# bms_ver0_2.net
KiCad netlist of a schematic drawn in EAGLE
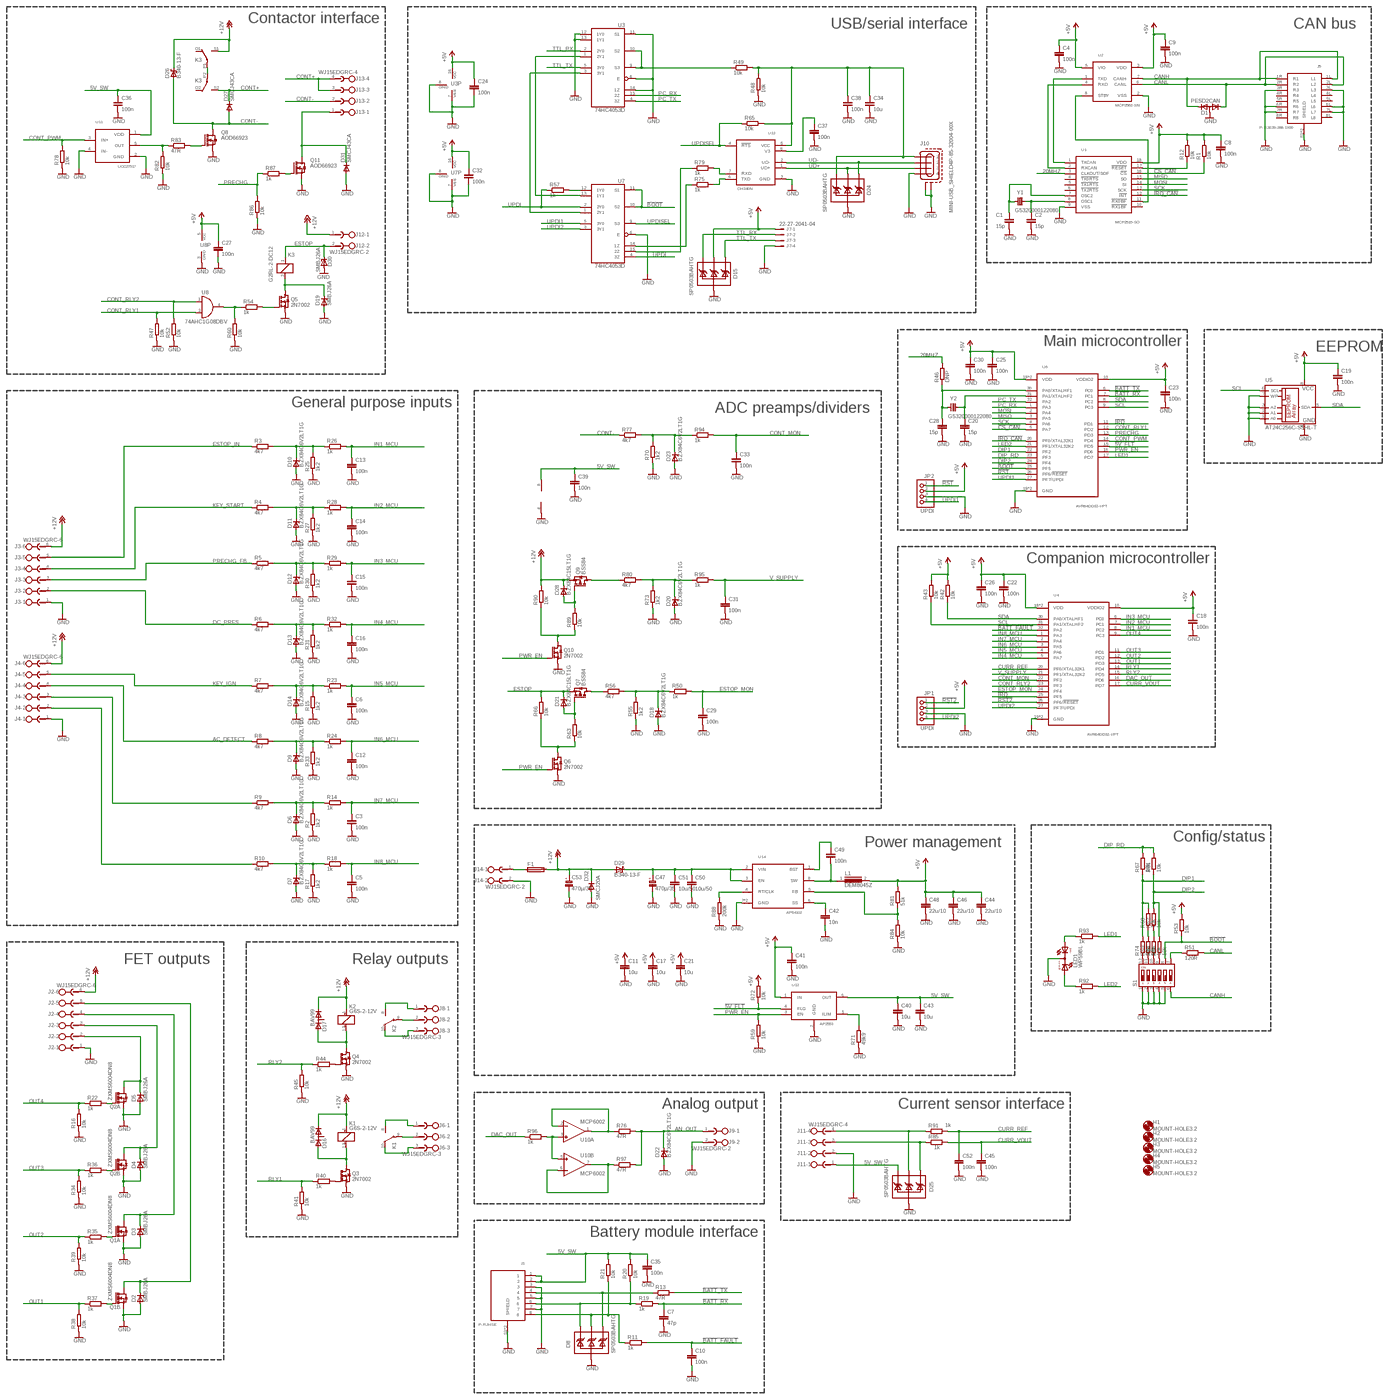
[diagram p0: schematic, sheet 1, overview]
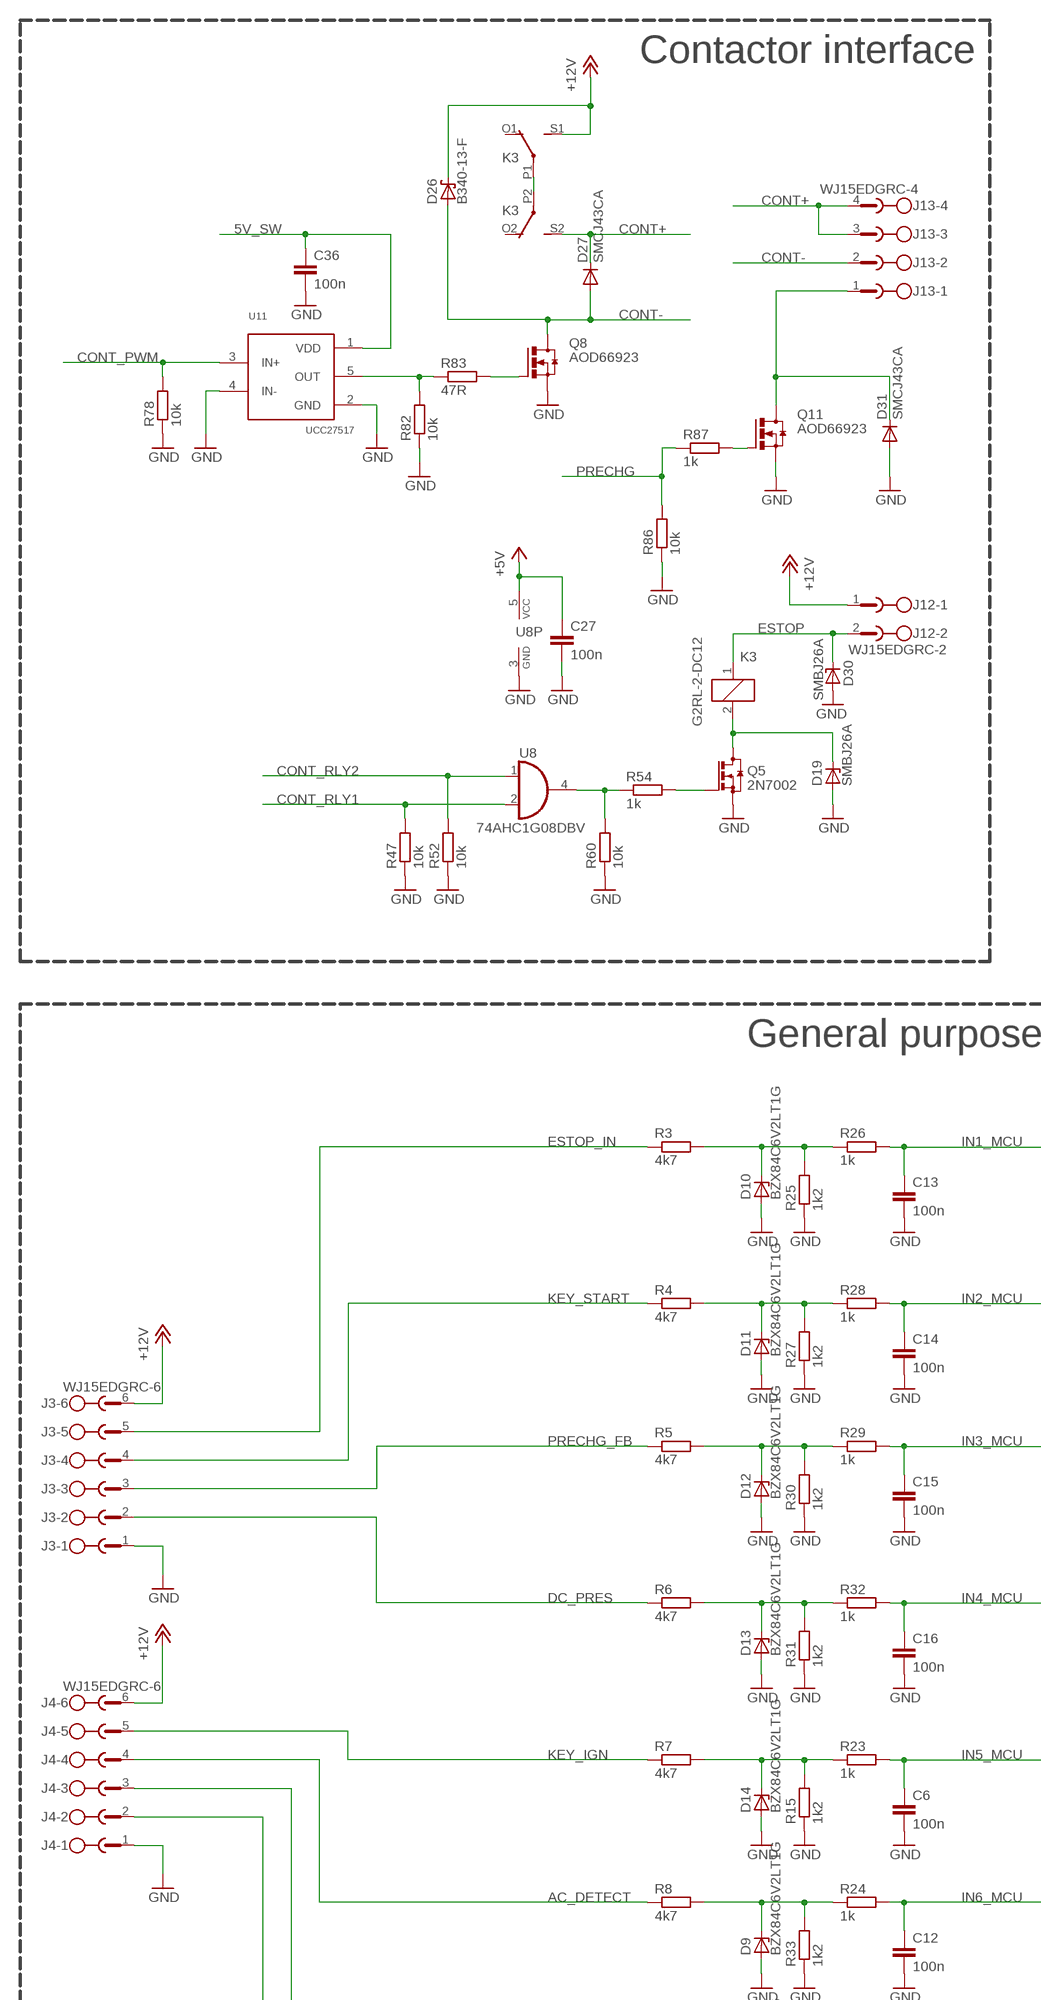
[diagram p1: schematic, sheet 1, part 1 of 4]
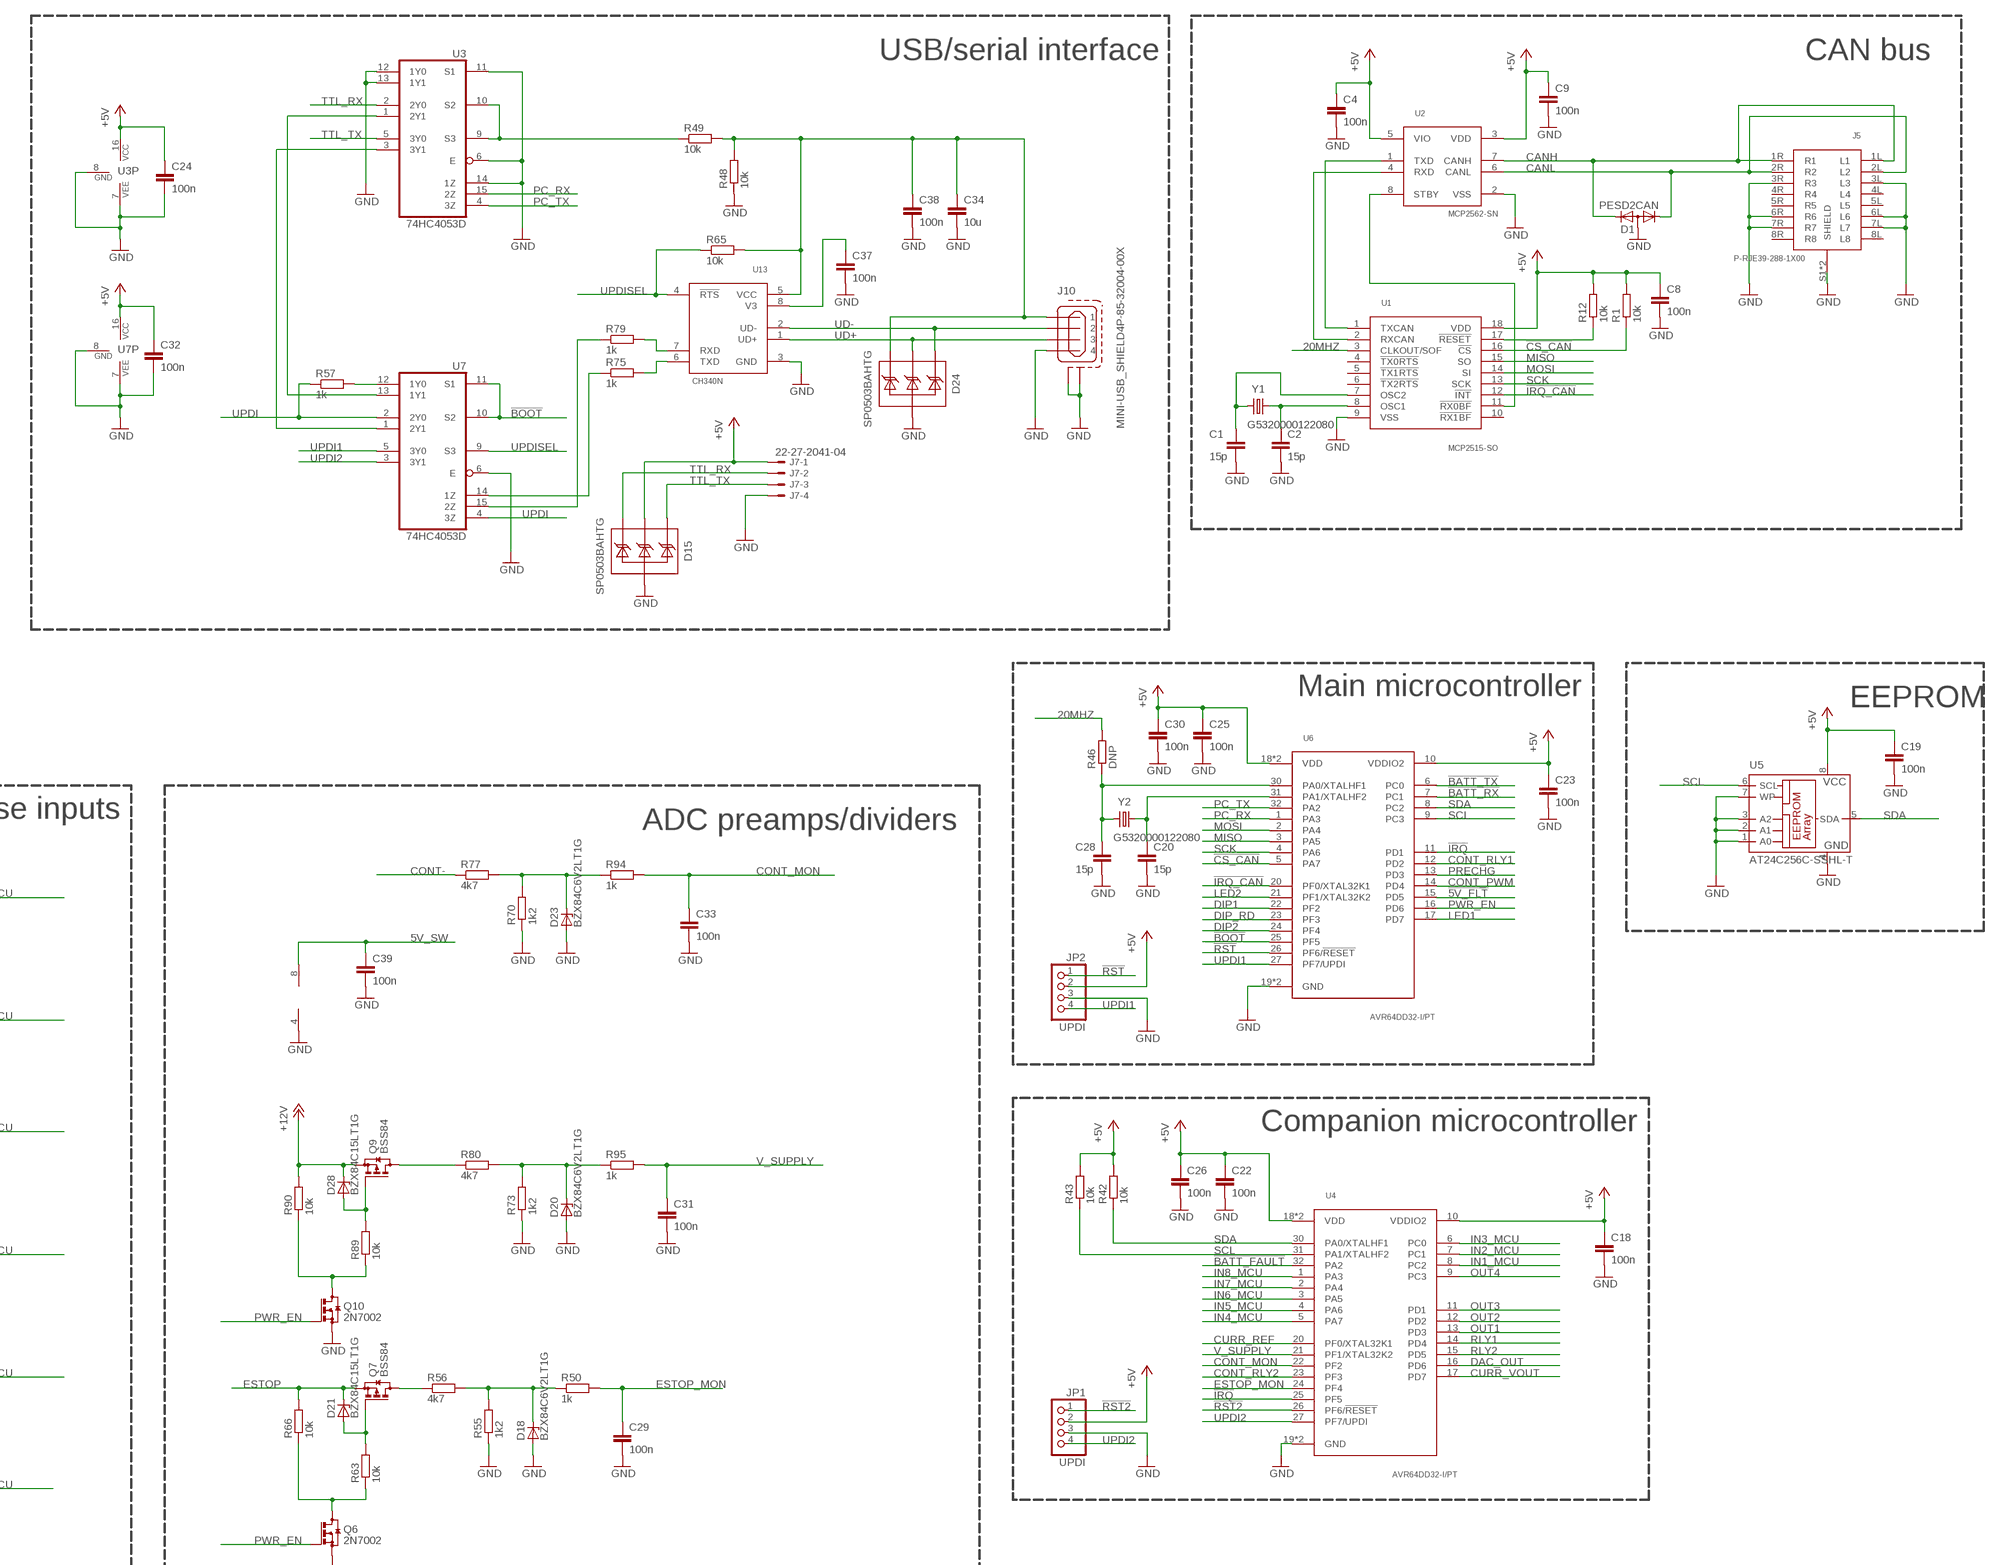
[diagram p2: schematic, sheet 1, part 2 of 4]
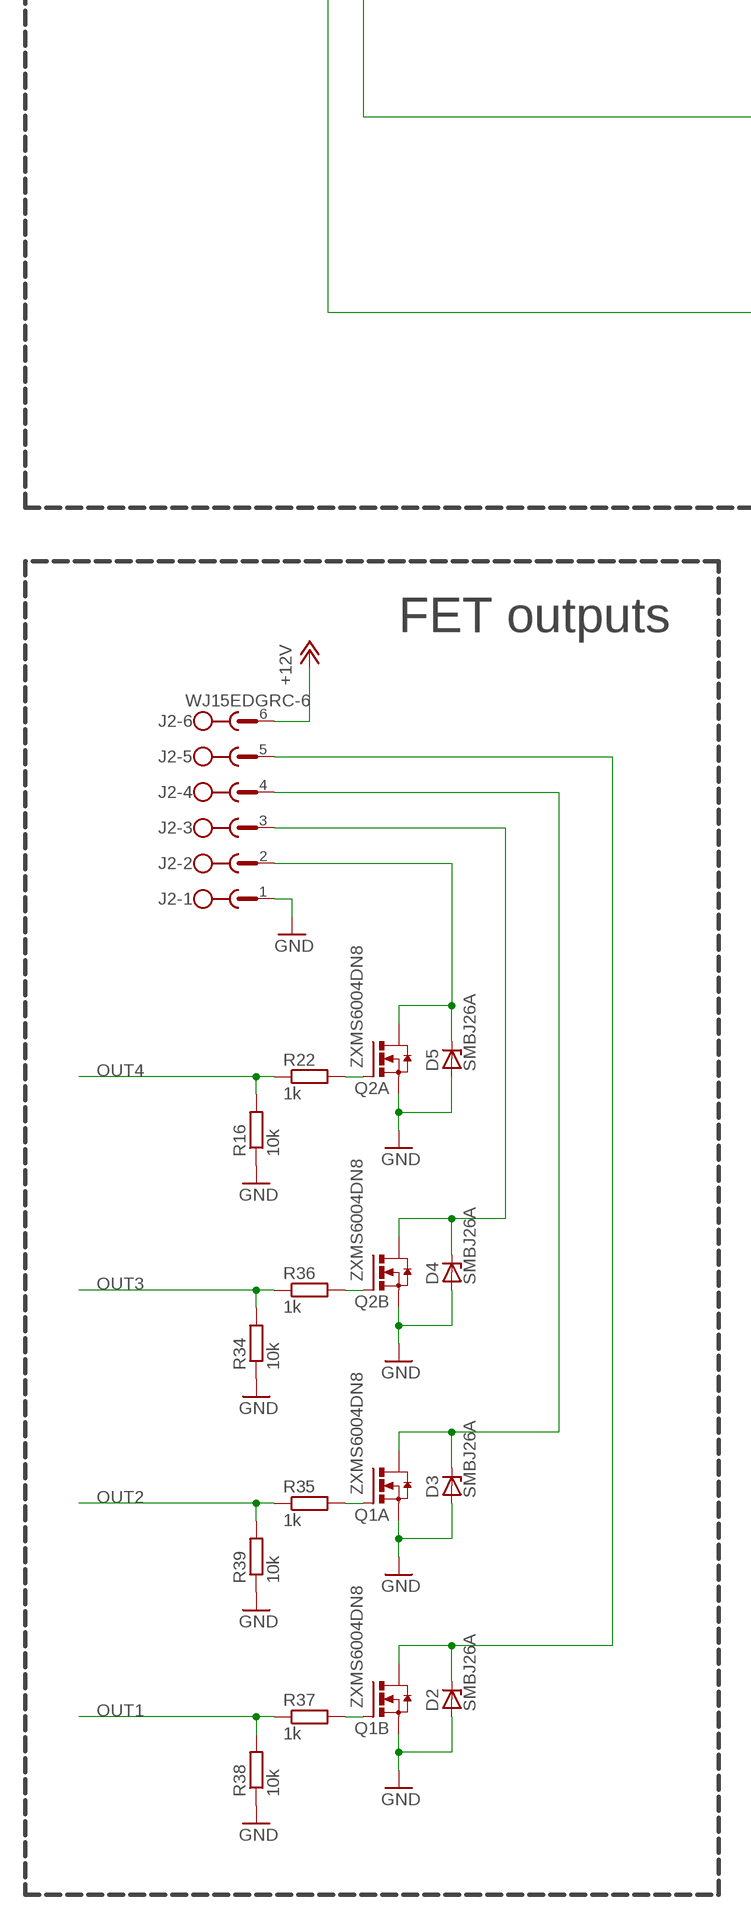
[diagram p3: schematic, sheet 1, part 3 of 4]
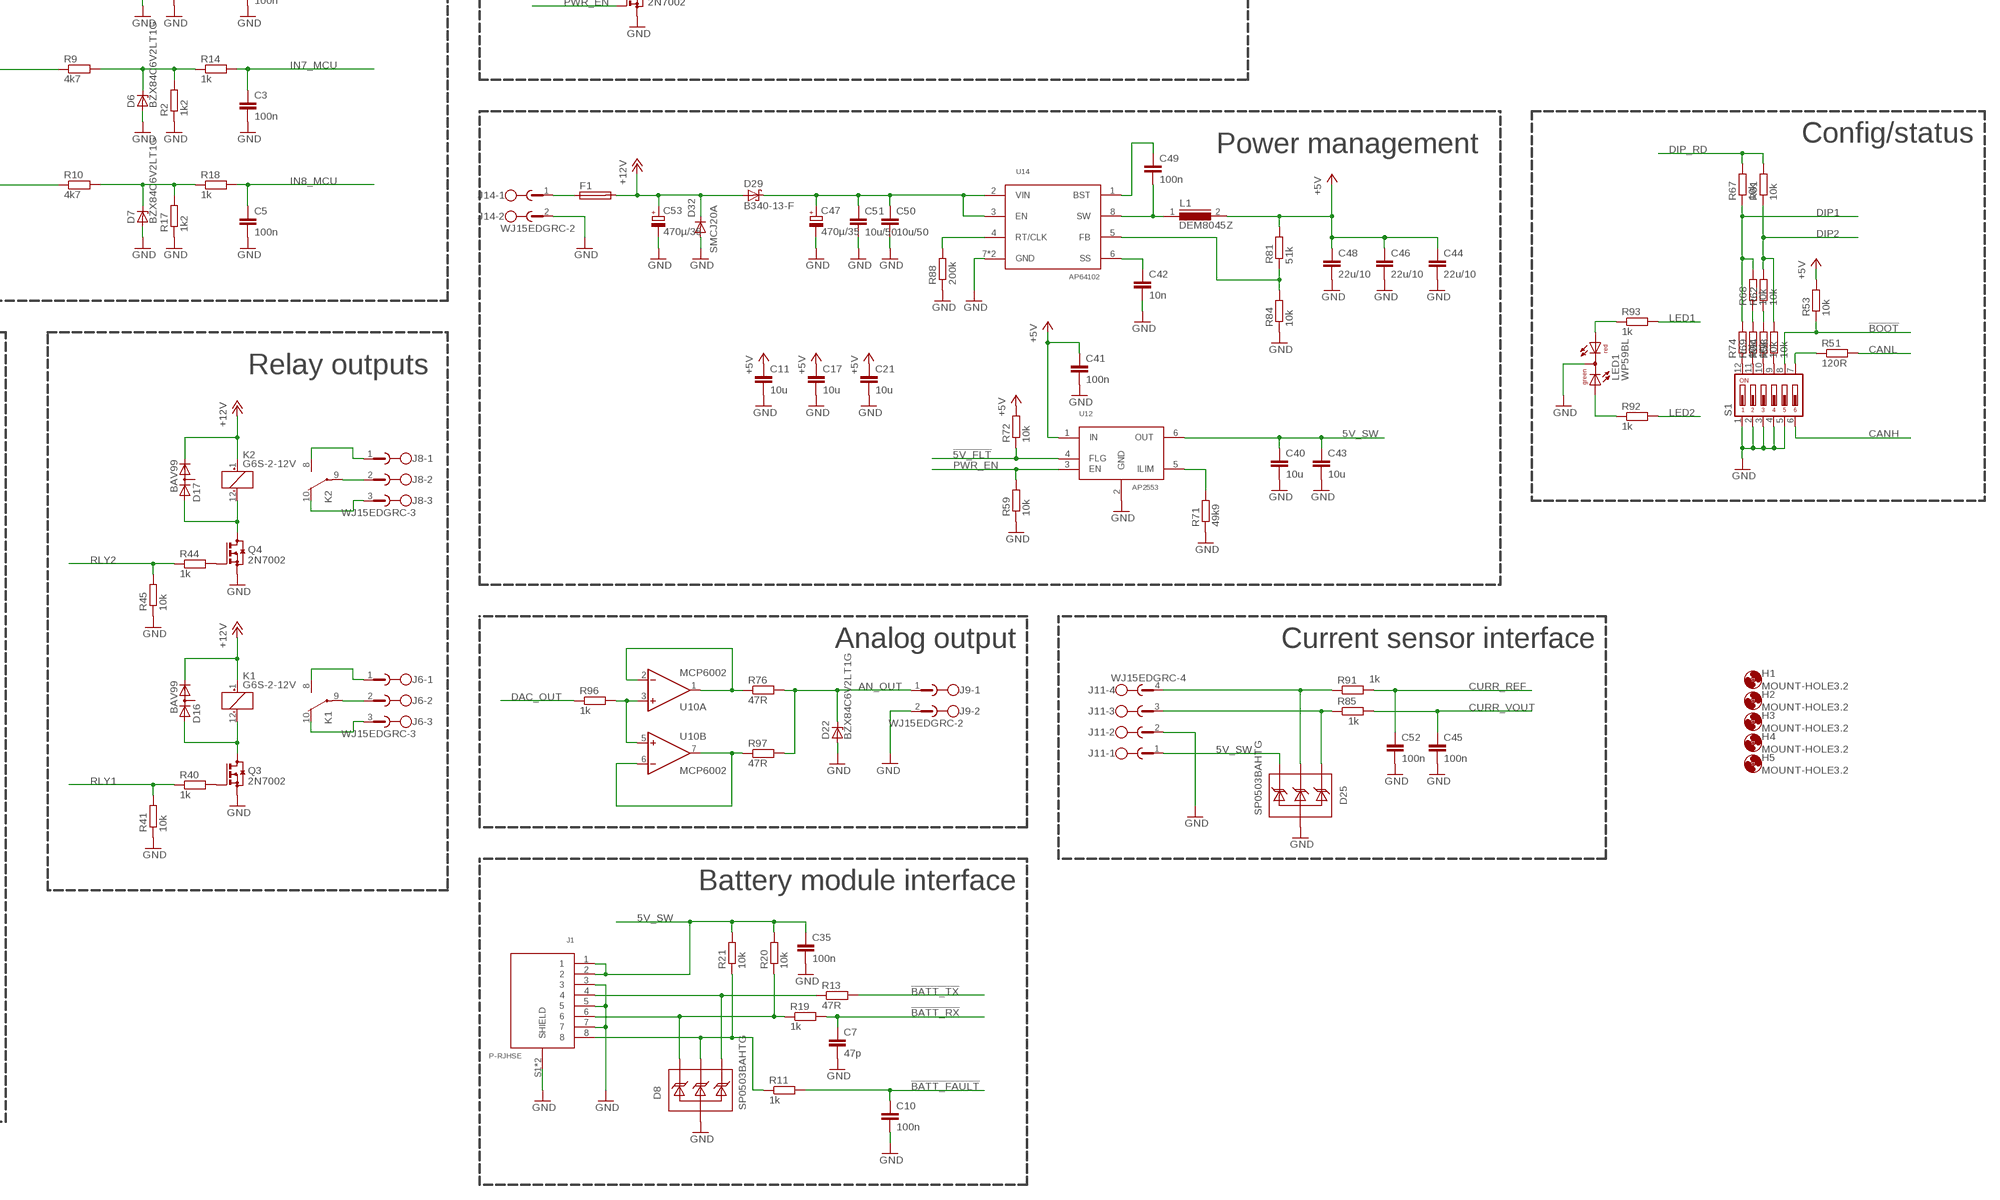
[diagram p4: schematic, sheet 1, part 4 of 4]

(export (version "E")
  (design (tool "Eeschema 10.0.6"))
  (components
    (comp (ref "C1")
      (value "15p")
      (footprint "eagle-import:C0805K")
      (libsource (lib "eagle-import") (part "C-EUC0805K"))
    )
    (comp (ref "C2")
      (value "15p")
      (footprint "eagle-import:C0805K")
      (libsource (lib "eagle-import") (part "C-EUC0805K"))
    )
    (comp (ref "C3")
      (value "100n")
      (footprint "eagle-import:C0805K")
      (libsource (lib "eagle-import") (part "C-EUC0805K"))
    )
    (comp (ref "C4")
      (value "100n")
      (footprint "eagle-import:C0805K")
      (libsource (lib "eagle-import") (part "C-EUC0805K"))
    )
    (comp (ref "C5")
      (value "100n")
      (footprint "eagle-import:C0805K")
      (libsource (lib "eagle-import") (part "C-EUC0805K"))
    )
    (comp (ref "C6")
      (value "100n")
      (footprint "eagle-import:C0805K")
      (libsource (lib "eagle-import") (part "C-EUC0805K"))
    )
    (comp (ref "C7")
      (value "47p")
      (footprint "eagle-import:C0805K")
      (libsource (lib "eagle-import") (part "C-EUC0805K"))
    )
    (comp (ref "C8")
      (value "100n")
      (footprint "eagle-import:C0805K")
      (libsource (lib "eagle-import") (part "C-EUC0805K"))
    )
    (comp (ref "C9")
      (value "100n")
      (footprint "eagle-import:C0805K")
      (libsource (lib "eagle-import") (part "C-EUC0805K"))
    )
    (comp (ref "C10")
      (value "100n")
      (footprint "eagle-import:C0805K")
      (libsource (lib "eagle-import") (part "C-EUC0805K"))
    )
    (comp (ref "C11")
      (value "10u")
      (footprint "eagle-import:C1206K")
      (libsource (lib "eagle-import") (part "C-EUC1206K"))
    )
    (comp (ref "C12")
      (value "100n")
      (footprint "eagle-import:C0805K")
      (libsource (lib "eagle-import") (part "C-EUC0805K"))
    )
    (comp (ref "C13")
      (value "100n")
      (footprint "eagle-import:C0805K")
      (libsource (lib "eagle-import") (part "C-EUC0805K"))
    )
    (comp (ref "C14")
      (value "100n")
      (footprint "eagle-import:C0805K")
      (libsource (lib "eagle-import") (part "C-EUC0805K"))
    )
    (comp (ref "C15")
      (value "100n")
      (footprint "eagle-import:C0805K")
      (libsource (lib "eagle-import") (part "C-EUC0805K"))
    )
    (comp (ref "C16")
      (value "100n")
      (footprint "eagle-import:C0805K")
      (libsource (lib "eagle-import") (part "C-EUC0805K"))
    )
    (comp (ref "C17")
      (value "10u")
      (footprint "eagle-import:C1206K")
      (libsource (lib "eagle-import") (part "C-EUC1206K"))
    )
    (comp (ref "C18")
      (value "100n")
      (footprint "eagle-import:C0805K")
      (libsource (lib "eagle-import") (part "C-EUC0805K"))
    )
    (comp (ref "C19")
      (value "100n")
      (footprint "eagle-import:C0805K")
      (libsource (lib "eagle-import") (part "C-EUC0805K"))
    )
    (comp (ref "C20")
      (value "15p")
      (footprint "eagle-import:C0805K")
      (libsource (lib "eagle-import") (part "C-EUC0805K"))
    )
    (comp (ref "C21")
      (value "10u")
      (footprint "eagle-import:C1206K")
      (libsource (lib "eagle-import") (part "C-EUC1206K"))
    )
    (comp (ref "C22")
      (value "100n")
      (footprint "eagle-import:C0805K")
      (libsource (lib "eagle-import") (part "C-EUC0805K"))
    )
    (comp (ref "C23")
      (value "100n")
      (footprint "eagle-import:C0805K")
      (libsource (lib "eagle-import") (part "C-EUC0805K"))
    )
    (comp (ref "C24")
      (value "100n")
      (footprint "eagle-import:C0805K")
      (libsource (lib "eagle-import") (part "C-EUC0805K"))
    )
    (comp (ref "C25")
      (value "100n")
      (footprint "eagle-import:C0805K")
      (libsource (lib "eagle-import") (part "C-EUC0805K"))
    )
    (comp (ref "C26")
      (value "100n")
      (footprint "eagle-import:C0805K")
      (libsource (lib "eagle-import") (part "C-EUC0805K"))
    )
    (comp (ref "C27")
      (value "100n")
      (footprint "eagle-import:C0805K")
      (libsource (lib "eagle-import") (part "C-EUC0805K"))
    )
    (comp (ref "C28")
      (value "15p")
      (footprint "eagle-import:C0805K")
      (libsource (lib "eagle-import") (part "C-EUC0805K"))
    )
    (comp (ref "C29")
      (value "100n")
      (footprint "eagle-import:C0805K")
      (libsource (lib "eagle-import") (part "C-EUC0805K"))
    )
    (comp (ref "C30")
      (value "100n")
      (footprint "eagle-import:C0805K")
      (libsource (lib "eagle-import") (part "C-EUC0805K"))
    )
    (comp (ref "C31")
      (value "100n")
      (footprint "eagle-import:C0805K")
      (libsource (lib "eagle-import") (part "C-EUC0805K"))
    )
    (comp (ref "C32")
      (value "100n")
      (footprint "eagle-import:C0805K")
      (libsource (lib "eagle-import") (part "C-EUC0805K"))
    )
    (comp (ref "C33")
      (value "100n")
      (footprint "eagle-import:C0805K")
      (libsource (lib "eagle-import") (part "C-EUC0805K"))
    )
    (comp (ref "C34")
      (value "10u")
      (footprint "eagle-import:C1206K")
      (libsource (lib "eagle-import") (part "C-EUC1206K"))
    )
    (comp (ref "C35")
      (value "100n")
      (footprint "eagle-import:C0805K")
      (libsource (lib "eagle-import") (part "C-EUC0805K"))
    )
    (comp (ref "C36")
      (value "100n")
      (footprint "eagle-import:C0805K")
      (libsource (lib "eagle-import") (part "C-EUC0805K"))
    )
    (comp (ref "C37")
      (value "100n")
      (footprint "eagle-import:C0805K")
      (libsource (lib "eagle-import") (part "C-EUC0805K"))
    )
    (comp (ref "C38")
      (value "100n")
      (footprint "eagle-import:C0805K")
      (libsource (lib "eagle-import") (part "C-EUC0805K"))
    )
    (comp (ref "C39")
      (value "100n")
      (footprint "eagle-import:C0805K")
      (libsource (lib "eagle-import") (part "C-EUC0805K"))
    )
    (comp (ref "C40")
      (value "10u")
      (footprint "eagle-import:C1206K")
      (libsource (lib "eagle-import") (part "C-EUC1206K"))
    )
    (comp (ref "C41")
      (value "100n")
      (footprint "eagle-import:C0805K")
      (libsource (lib "eagle-import") (part "C-EUC0805K"))
    )
    (comp (ref "C42")
      (value "10n")
      (footprint "eagle-import:C0805K")
      (libsource (lib "eagle-import") (part "C-EUC0805K"))
    )
    (comp (ref "C43")
      (value "10u")
      (footprint "eagle-import:C1206K")
      (libsource (lib "eagle-import") (part "C-EUC1206K"))
    )
    (comp (ref "C44")
      (value "22u/10")
      (footprint "eagle-import:C1206K")
      (libsource (lib "eagle-import") (part "C-EUC1206K"))
    )
    (comp (ref "C45")
      (value "100n")
      (footprint "eagle-import:C0805K")
      (libsource (lib "eagle-import") (part "C-EUC0805K"))
    )
    (comp (ref "C46")
      (value "22u/10")
      (footprint "eagle-import:C1206K")
      (libsource (lib "eagle-import") (part "C-EUC1206K"))
    )
    (comp (ref "C47")
      (value "470µ/35")
      (footprint "eagle-import:E5-10,5")
      (libsource (lib "eagle-import") (part "CPOL-EUE5-10.5"))
    )
    (comp (ref "C48")
      (value "22u/10")
      (footprint "eagle-import:C1206K")
      (libsource (lib "eagle-import") (part "C-EUC1206K"))
    )
    (comp (ref "C49")
      (value "100n")
      (footprint "eagle-import:C0805K")
      (libsource (lib "eagle-import") (part "C-EUC0805K"))
    )
    (comp (ref "C50")
      (value "10u/50")
      (footprint "eagle-import:C1206K")
      (libsource (lib "eagle-import") (part "C-EUC1206K"))
    )
    (comp (ref "C51")
      (value "10u/50")
      (footprint "eagle-import:C1206K")
      (libsource (lib "eagle-import") (part "C-EUC1206K"))
    )
    (comp (ref "C52")
      (value "100n")
      (footprint "eagle-import:C0805K")
      (libsource (lib "eagle-import") (part "C-EUC0805K"))
    )
    (comp (ref "C53")
      (value "470µ/35")
      (footprint "eagle-import:E5-10,5")
      (libsource (lib "eagle-import") (part "CPOL-EUE5-10.5"))
    )
    (comp (ref "D1")
      (value "PESD2CAN")
      (footprint "eagle-import:SOT23")
      (libsource (lib "eagle-import") (part "DIODE-2CA|ACSOT23"))
    )
    (comp (ref "D2")
      (value "SMBJ26A")
      (footprint "eagle-import:SMB")
      (libsource (lib "eagle-import") (part "ZENER-DIODESMB"))
    )
    (comp (ref "D3")
      (value "SMBJ26A")
      (footprint "eagle-import:SMB")
      (libsource (lib "eagle-import") (part "ZENER-DIODESMB"))
    )
    (comp (ref "D4")
      (value "SMBJ26A")
      (footprint "eagle-import:SMB")
      (libsource (lib "eagle-import") (part "ZENER-DIODESMB"))
    )
    (comp (ref "D5")
      (value "SMBJ26A")
      (footprint "eagle-import:SMB")
      (libsource (lib "eagle-import") (part "ZENER-DIODESMB"))
    )
    (comp (ref "D6")
      (value "BZX84C6V2LT1G")
      (footprint "eagle-import:SOT23")
      (libsource (lib "eagle-import") (part "ZENER-DIODESOT23"))
    )
    (comp (ref "D7")
      (value "BZX84C6V2LT1G")
      (footprint "eagle-import:SOT23")
      (libsource (lib "eagle-import") (part "ZENER-DIODESOT23"))
    )
    (comp (ref "D8")
      (value "SP0503BAHTG")
      (footprint "eagle-import:SOT143")
      (libsource (lib "eagle-import") (part "SP0503BAHTG"))
    )
    (comp (ref "D9")
      (value "BZX84C6V2LT1G")
      (footprint "eagle-import:SOT23")
      (libsource (lib "eagle-import") (part "ZENER-DIODESOT23"))
    )
    (comp (ref "D10")
      (value "BZX84C6V2LT1G")
      (footprint "eagle-import:SOT23")
      (libsource (lib "eagle-import") (part "ZENER-DIODESOT23"))
    )
    (comp (ref "D11")
      (value "BZX84C6V2LT1G")
      (footprint "eagle-import:SOT23")
      (libsource (lib "eagle-import") (part "ZENER-DIODESOT23"))
    )
    (comp (ref "D12")
      (value "BZX84C6V2LT1G")
      (footprint "eagle-import:SOT23")
      (libsource (lib "eagle-import") (part "ZENER-DIODESOT23"))
    )
    (comp (ref "D13")
      (value "BZX84C6V2LT1G")
      (footprint "eagle-import:SOT23")
      (libsource (lib "eagle-import") (part "ZENER-DIODESOT23"))
    )
    (comp (ref "D14")
      (value "BZX84C6V2LT1G")
      (footprint "eagle-import:SOT23")
      (libsource (lib "eagle-import") (part "ZENER-DIODESOT23"))
    )
    (comp (ref "D15")
      (value "SP0503BAHTG")
      (footprint "eagle-import:SOT143")
      (libsource (lib "eagle-import") (part "SP0503BAHTG"))
    )
    (comp (ref "D16")
      (value "BAV99")
      (footprint "eagle-import:SOT23")
      (libsource (lib "eagle-import") (part "BAV199"))
    )
    (comp (ref "D17")
      (value "BAV99")
      (footprint "eagle-import:SOT23")
      (libsource (lib "eagle-import") (part "BAV199"))
    )
    (comp (ref "D18")
      (value "BZX84C6V2LT1G")
      (footprint "eagle-import:SOT23")
      (libsource (lib "eagle-import") (part "ZENER-DIODESOT23"))
    )
    (comp (ref "D19")
      (value "SMBJ26A")
      (footprint "eagle-import:SMB")
      (libsource (lib "eagle-import") (part "ZENER-DIODESMB"))
    )
    (comp (ref "D20")
      (value "BZX84C6V2LT1G")
      (footprint "eagle-import:SOT23")
      (libsource (lib "eagle-import") (part "ZENER-DIODESOT23"))
    )
    (comp (ref "D21")
      (value "BZX84C15LT1G")
      (footprint "eagle-import:SOT23")
      (libsource (lib "eagle-import") (part "ZENER-DIODESOT23"))
    )
    (comp (ref "D22")
      (value "BZX84C6V2LT1G")
      (footprint "eagle-import:SOT23")
      (libsource (lib "eagle-import") (part "ZENER-DIODESOT23"))
    )
    (comp (ref "D23")
      (value "BZX84C6V2LT1G")
      (footprint "eagle-import:SOT23")
      (libsource (lib "eagle-import") (part "ZENER-DIODESOT23"))
    )
    (comp (ref "D24")
      (value "SP0503BAHTG")
      (footprint "eagle-import:SOT143")
      (libsource (lib "eagle-import") (part "SP0503BAHTG"))
    )
    (comp (ref "D25")
      (value "SP0503BAHTG")
      (footprint "eagle-import:SOT143")
      (libsource (lib "eagle-import") (part "SP0503BAHTG"))
    )
    (comp (ref "D26")
      (value "B340-13-F")
      (footprint "eagle-import:SMC")
      (libsource (lib "eagle-import") (part "SCHOTTKY-DIODESMC"))
    )
    (comp (ref "D27")
      (value "SMCJ43CA")
      (footprint "eagle-import:SMC")
      (libsource (lib "eagle-import") (part "DIODE-SMC"))
    )
    (comp (ref "D28")
      (value "BZX84C15LT1G")
      (footprint "eagle-import:SOT23")
      (libsource (lib "eagle-import") (part "ZENER-DIODESOT23"))
    )
    (comp (ref "D29")
      (value "B340-13-F")
      (footprint "eagle-import:SMC")
      (libsource (lib "eagle-import") (part "SCHOTTKY-DIODESMC"))
    )
    (comp (ref "D30")
      (value "SMBJ26A")
      (footprint "eagle-import:SMB")
      (libsource (lib "eagle-import") (part "ZENER-DIODESMB"))
    )
    (comp (ref "D31")
      (value "SMCJ43CA")
      (footprint "eagle-import:SMC")
      (libsource (lib "eagle-import") (part "DIODE-SMC"))
    )
    (comp (ref "D32")
      (value "SMCJ20A")
      (footprint "eagle-import:SMC")
      (libsource (lib "eagle-import") (part "DIODE-SMC"))
    )
    (comp (ref "F1")
      (value "3568")
      (footprint "eagle-import:3568")
      (libsource (lib "eagle-import") (part "3568"))
    )
    (comp (ref "H1")
      (value "MOUNT-HOLE3.2")
      (footprint "eagle-import:3,2")
      (libsource (lib "eagle-import") (part "MOUNT-HOLE3.2"))
    )
    (comp (ref "H2")
      (value "MOUNT-HOLE3.2")
      (footprint "eagle-import:3,2")
      (libsource (lib "eagle-import") (part "MOUNT-HOLE3.2"))
    )
    (comp (ref "H3")
      (value "MOUNT-HOLE3.2")
      (footprint "eagle-import:3,2")
      (libsource (lib "eagle-import") (part "MOUNT-HOLE3.2"))
    )
    (comp (ref "H4")
      (value "MOUNT-HOLE3.2")
      (footprint "eagle-import:3,2")
      (libsource (lib "eagle-import") (part "MOUNT-HOLE3.2"))
    )
    (comp (ref "H5")
      (value "MOUNT-HOLE3.2")
      (footprint "eagle-import:3,2")
      (libsource (lib "eagle-import") (part "MOUNT-HOLE3.2"))
    )
    (comp (ref "J1")
      (value "P-RJHSE")
      (footprint "eagle-import:P-RJHSE")
      (libsource (lib "eagle-import") (part "P-RJHSE"))
    )
    (comp (ref "J2")
      (value "WJ15EDGRC-6")
      (footprint "eagle-import:WJ15EDGRC-3.81-6")
      (libsource (lib "eagle-import") (part "WJ15EDGRC-6"))
    )
    (comp (ref "J3")
      (value "WJ15EDGRC-6")
      (footprint "eagle-import:WJ15EDGRC-3.81-6")
      (libsource (lib "eagle-import") (part "WJ15EDGRC-6"))
    )
    (comp (ref "J4")
      (value "WJ15EDGRC-6")
      (footprint "eagle-import:WJ15EDGRC-3.81-6")
      (libsource (lib "eagle-import") (part "WJ15EDGRC-6"))
    )
    (comp (ref "J5")
      (value "P-RJE39-288-1X00")
      (footprint "eagle-import:P-RJE39-288-1X00")
      (libsource (lib "eagle-import") (part "P-RJE39-288-1X00"))
    )
    (comp (ref "J6")
      (value "WJ15EDGRC-3")
      (footprint "eagle-import:WJ15EDGRC-3.81-3")
      (libsource (lib "eagle-import") (part "WJ15EDGRC-3"))
    )
    (comp (ref "J7")
      (value "22-27-2041-04")
      (footprint "eagle-import:6410-04")
      (libsource (lib "eagle-import") (part "22-?-0427-2041"))
    )
    (comp (ref "J8")
      (value "WJ15EDGRC-3")
      (footprint "eagle-import:WJ15EDGRC-3.81-3")
      (libsource (lib "eagle-import") (part "WJ15EDGRC-3"))
    )
    (comp (ref "J9")
      (value "WJ15EDGRC-2")
      (footprint "eagle-import:WJ15EDGRC-3.81-2")
      (libsource (lib "eagle-import") (part "WJ15EDGRC-2"))
    )
    (comp (ref "J10")
      (value "MINI-USB_SHIELD4P-85-32004-00X")
      (footprint "eagle-import:85-32004-00X")
      (libsource (lib "eagle-import") (part "MINI-USB_SHIELD4P-85-32004-00X"))
    )
    (comp (ref "J11")
      (value "WJ15EDGRC-4")
      (footprint "eagle-import:WJ15EDGRC-3.81-4")
      (libsource (lib "eagle-import") (part "WJ15EDGRC-4"))
    )
    (comp (ref "J12")
      (value "WJ15EDGRC-2")
      (footprint "eagle-import:WJ15EDGRC-3.81-2")
      (libsource (lib "eagle-import") (part "WJ15EDGRC-2"))
    )
    (comp (ref "J13")
      (value "WJ15EDGRC-4")
      (footprint "eagle-import:WJ15EDGRC-3.81-4")
      (libsource (lib "eagle-import") (part "WJ15EDGRC-4"))
    )
    (comp (ref "J14")
      (value "WJ15EDGRC-2")
      (footprint "eagle-import:WJ15EDGRC-3.81-2")
      (libsource (lib "eagle-import") (part "WJ15EDGRC-2"))
    )
    (comp (ref "JP1")
      (value "UPDI")
      (footprint "eagle-import:1X04")
      (libsource (lib "eagle-import") (part "PINHD-1X4"))
    )
    (comp (ref "JP2")
      (value "UPDI")
      (footprint "eagle-import:1X04")
      (libsource (lib "eagle-import") (part "PINHD-1X4"))
    )
    (comp (ref "K1")
      (value "G6S-2-12V")
      (footprint "eagle-import:TXD2")
      (fields (field (name "MPN") "TXS2-12V"))
      (libsource (lib "eagle-import") (part "TX?-S212V"))
    )
    (comp (ref "K2")
      (value "G6S-2-12V")
      (footprint "eagle-import:TXD2")
      (fields (field (name "MPN") "TXS2-12V"))
      (libsource (lib "eagle-import") (part "TX?-S212V"))
    )
    (comp (ref "K3")
      (value "G2RL-2-DC12")
      (footprint "eagle-import:G2R2")
      (fields (field (name "MF") "OMRON COMPONENTS USA") (field (name "MPN") "G2R-2-DC6"))
      (libsource (lib "eagle-import") (part "G2R2"))
    )
    (comp (ref "L1")
      (value "DEM8045Z")
      (footprint "eagle-import:DEM8045Z")
      (libsource (lib "eagle-import") (part "DEM8045Z"))
    )
    (comp (ref "LED1")
      (value "WP59BL")
      (footprint "eagle-import:WP59BL")
      (fields (field (name "MF") "VISHAY SEMICONDUCTOR"))
      (libsource (lib "eagle-import") (part "WP59BL"))
    )
    (comp (ref "Q1")
      (value "ZXMS6004DN8")
      (footprint "eagle-import:SO-08")
      (fields (field (name "MOUSER") "621-ZXMS6004DN8-13"))
      (libsource (lib "eagle-import") (part "IRF8313P"))
    )
    (comp (ref "Q2")
      (value "ZXMS6004DN8")
      (footprint "eagle-import:SO-08")
      (fields (field (name "MOUSER") "621-ZXMS6004DN8-13"))
      (libsource (lib "eagle-import") (part "IRF8313P"))
    )
    (comp (ref "Q3")
      (value "2N7002")
      (footprint "eagle-import:SOT23")
      (libsource (lib "eagle-import") (part "BSS123"))
    )
    (comp (ref "Q4")
      (value "2N7002")
      (footprint "eagle-import:SOT23")
      (libsource (lib "eagle-import") (part "BSS123"))
    )
    (comp (ref "Q5")
      (value "2N7002")
      (footprint "eagle-import:SOT23")
      (libsource (lib "eagle-import") (part "BSS123"))
    )
    (comp (ref "Q6")
      (value "2N7002")
      (footprint "eagle-import:SOT23")
      (libsource (lib "eagle-import") (part "BSS123"))
    )
    (comp (ref "Q7")
      (value "BSS84")
      (footprint "eagle-import:SOT23")
      (libsource (lib "eagle-import") (part "BSS84"))
    )
    (comp (ref "Q8")
      (value "AOD66923")
      (footprint "eagle-import:D-PAK_TO252AA")
      (libsource (lib "eagle-import") (part "N-MOSFETR"))
    )
    (comp (ref "Q9")
      (value "BSS84")
      (footprint "eagle-import:SOT23")
      (libsource (lib "eagle-import") (part "BSS84"))
    )
    (comp (ref "Q10")
      (value "2N7002")
      (footprint "eagle-import:SOT23")
      (libsource (lib "eagle-import") (part "BSS123"))
    )
    (comp (ref "Q11")
      (value "AOD66923")
      (footprint "eagle-import:D-PAK_TO252AA")
      (libsource (lib "eagle-import") (part "N-MOSFETR"))
    )
    (comp (ref "R1")
      (value "10k")
      (footprint "eagle-import:R0805")
      (libsource (lib "eagle-import") (part "R-EU_R0805"))
    )
    (comp (ref "R2")
      (value "1k2")
      (footprint "eagle-import:R0805")
      (libsource (lib "eagle-import") (part "R-EU_R0805"))
    )
    (comp (ref "R3")
      (value "4k7")
      (footprint "eagle-import:R1206")
      (libsource (lib "eagle-import") (part "R-EU_R1206"))
    )
    (comp (ref "R4")
      (value "4k7")
      (footprint "eagle-import:R1206")
      (libsource (lib "eagle-import") (part "R-EU_R1206"))
    )
    (comp (ref "R5")
      (value "4k7")
      (footprint "eagle-import:R1206")
      (libsource (lib "eagle-import") (part "R-EU_R1206"))
    )
    (comp (ref "R6")
      (value "4k7")
      (footprint "eagle-import:R1206")
      (libsource (lib "eagle-import") (part "R-EU_R1206"))
    )
    (comp (ref "R7")
      (value "4k7")
      (footprint "eagle-import:R1206")
      (libsource (lib "eagle-import") (part "R-EU_R1206"))
    )
    (comp (ref "R8")
      (value "4k7")
      (footprint "eagle-import:R1206")
      (libsource (lib "eagle-import") (part "R-EU_R1206"))
    )
    (comp (ref "R9")
      (value "4k7")
      (footprint "eagle-import:R1206")
      (libsource (lib "eagle-import") (part "R-EU_R1206"))
    )
    (comp (ref "R10")
      (value "4k7")
      (footprint "eagle-import:R1206")
      (libsource (lib "eagle-import") (part "R-EU_R1206"))
    )
    (comp (ref "R11")
      (value "1k")
      (footprint "eagle-import:R0805")
      (libsource (lib "eagle-import") (part "R-EU_R0805"))
    )
    (comp (ref "R12")
      (value "10k")
      (footprint "eagle-import:R0805")
      (libsource (lib "eagle-import") (part "R-EU_R0805"))
    )
    (comp (ref "R13")
      (value "47R")
      (footprint "eagle-import:R0805")
      (libsource (lib "eagle-import") (part "R-EU_R0805"))
    )
    (comp (ref "R14")
      (value "1k")
      (footprint "eagle-import:R0805")
      (libsource (lib "eagle-import") (part "R-EU_R0805"))
    )
    (comp (ref "R15")
      (value "1k2")
      (footprint "eagle-import:R0805")
      (libsource (lib "eagle-import") (part "R-EU_R0805"))
    )
    (comp (ref "R16")
      (value "10k")
      (footprint "eagle-import:R0805")
      (libsource (lib "eagle-import") (part "R-EU_R0805"))
    )
    (comp (ref "R17")
      (value "1k2")
      (footprint "eagle-import:R0805")
      (libsource (lib "eagle-import") (part "R-EU_R0805"))
    )
    (comp (ref "R18")
      (value "1k")
      (footprint "eagle-import:R0805")
      (libsource (lib "eagle-import") (part "R-EU_R0805"))
    )
    (comp (ref "R19")
      (value "1k")
      (footprint "eagle-import:R0805")
      (libsource (lib "eagle-import") (part "R-EU_R0805"))
    )
    (comp (ref "R20")
      (value "10k")
      (footprint "eagle-import:R0805")
      (libsource (lib "eagle-import") (part "R-EU_R0805"))
    )
    (comp (ref "R21")
      (value "10k")
      (footprint "eagle-import:R0805")
      (libsource (lib "eagle-import") (part "R-EU_R0805"))
    )
    (comp (ref "R22")
      (value "1k")
      (footprint "eagle-import:R0805")
      (libsource (lib "eagle-import") (part "R-EU_R0805"))
    )
    (comp (ref "R23")
      (value "1k")
      (footprint "eagle-import:R0805")
      (libsource (lib "eagle-import") (part "R-EU_R0805"))
    )
    (comp (ref "R24")
      (value "1k")
      (footprint "eagle-import:R0805")
      (libsource (lib "eagle-import") (part "R-EU_R0805"))
    )
    (comp (ref "R25")
      (value "1k2")
      (footprint "eagle-import:R0805")
      (libsource (lib "eagle-import") (part "R-EU_R0805"))
    )
    (comp (ref "R26")
      (value "1k")
      (footprint "eagle-import:R0805")
      (libsource (lib "eagle-import") (part "R-EU_R0805"))
    )
    (comp (ref "R27")
      (value "1k2")
      (footprint "eagle-import:R0805")
      (libsource (lib "eagle-import") (part "R-EU_R0805"))
    )
    (comp (ref "R28")
      (value "1k")
      (footprint "eagle-import:R0805")
      (libsource (lib "eagle-import") (part "R-EU_R0805"))
    )
    (comp (ref "R29")
      (value "1k")
      (footprint "eagle-import:R0805")
      (libsource (lib "eagle-import") (part "R-EU_R0805"))
    )
    (comp (ref "R30")
      (value "1k2")
      (footprint "eagle-import:R0805")
      (libsource (lib "eagle-import") (part "R-EU_R0805"))
    )
    (comp (ref "R31")
      (value "1k2")
      (footprint "eagle-import:R0805")
      (libsource (lib "eagle-import") (part "R-EU_R0805"))
    )
    (comp (ref "R32")
      (value "1k")
      (footprint "eagle-import:R0805")
      (libsource (lib "eagle-import") (part "R-EU_R0805"))
    )
    (comp (ref "R33")
      (value "1k2")
      (footprint "eagle-import:R0805")
      (libsource (lib "eagle-import") (part "R-EU_R0805"))
    )
    (comp (ref "R34")
      (value "10k")
      (footprint "eagle-import:R0805")
      (libsource (lib "eagle-import") (part "R-EU_R0805"))
    )
    (comp (ref "R35")
      (value "1k")
      (footprint "eagle-import:R0805")
      (libsource (lib "eagle-import") (part "R-EU_R0805"))
    )
    (comp (ref "R36")
      (value "1k")
      (footprint "eagle-import:R0805")
      (libsource (lib "eagle-import") (part "R-EU_R0805"))
    )
    (comp (ref "R37")
      (value "1k")
      (footprint "eagle-import:R0805")
      (libsource (lib "eagle-import") (part "R-EU_R0805"))
    )
    (comp (ref "R38")
      (value "10k")
      (footprint "eagle-import:R0805")
      (libsource (lib "eagle-import") (part "R-EU_R0805"))
    )
    (comp (ref "R39")
      (value "10k")
      (footprint "eagle-import:R0805")
      (libsource (lib "eagle-import") (part "R-EU_R0805"))
    )
    (comp (ref "R40")
      (value "1k")
      (footprint "eagle-import:R0805")
      (libsource (lib "eagle-import") (part "R-EU_R0805"))
    )
    (comp (ref "R41")
      (value "10k")
      (footprint "eagle-import:R0805")
      (libsource (lib "eagle-import") (part "R-EU_R0805"))
    )
    (comp (ref "R42")
      (value "10k")
      (footprint "eagle-import:R0805")
      (libsource (lib "eagle-import") (part "R-EU_R0805"))
    )
    (comp (ref "R43")
      (value "10k")
      (footprint "eagle-import:R0805")
      (libsource (lib "eagle-import") (part "R-EU_R0805"))
    )
    (comp (ref "R44")
      (value "1k")
      (footprint "eagle-import:R0805")
      (libsource (lib "eagle-import") (part "R-EU_R0805"))
    )
    (comp (ref "R45")
      (value "10k")
      (footprint "eagle-import:R0805")
      (libsource (lib "eagle-import") (part "R-EU_R0805"))
    )
    (comp (ref "R46")
      (value "DNP")
      (footprint "eagle-import:R0805")
      (libsource (lib "eagle-import") (part "R-EU_R0805"))
    )
    (comp (ref "R47")
      (value "10k")
      (footprint "eagle-import:R0805")
      (libsource (lib "eagle-import") (part "R-EU_R0805"))
    )
    (comp (ref "R48")
      (value "10k")
      (footprint "eagle-import:R0805")
      (libsource (lib "eagle-import") (part "R-EU_R0805"))
    )
    (comp (ref "R49")
      (value "10k")
      (footprint "eagle-import:R0805")
      (libsource (lib "eagle-import") (part "R-EU_R0805"))
    )
    (comp (ref "R50")
      (value "1k")
      (footprint "eagle-import:R0805")
      (libsource (lib "eagle-import") (part "R-EU_R0805"))
    )
    (comp (ref "R51")
      (value "120R")
      (footprint "eagle-import:R1210")
      (libsource (lib "eagle-import") (part "R-EU_R1210"))
    )
    (comp (ref "R52")
      (value "10k")
      (footprint "eagle-import:R0805")
      (libsource (lib "eagle-import") (part "R-EU_R0805"))
    )
    (comp (ref "R53")
      (value "10k")
      (footprint "eagle-import:R0805")
      (libsource (lib "eagle-import") (part "R-EU_R0805"))
    )
    (comp (ref "R54")
      (value "1k")
      (footprint "eagle-import:R0805")
      (libsource (lib "eagle-import") (part "R-EU_R0805"))
    )
    (comp (ref "R55")
      (value "1k2")
      (footprint "eagle-import:R0805")
      (libsource (lib "eagle-import") (part "R-EU_R0805"))
    )
    (comp (ref "R56")
      (value "4k7")
      (footprint "eagle-import:R1206")
      (libsource (lib "eagle-import") (part "R-EU_R1206"))
    )
    (comp (ref "R57")
      (value "1k")
      (footprint "eagle-import:R0805")
      (libsource (lib "eagle-import") (part "R-EU_R0805"))
    )
    (comp (ref "R58")
      (value "10k")
      (footprint "eagle-import:R0805")
      (libsource (lib "eagle-import") (part "R-EU_R0805"))
    )
    (comp (ref "R59")
      (value "10k")
      (footprint "eagle-import:R0805")
      (libsource (lib "eagle-import") (part "R-EU_R0805"))
    )
    (comp (ref "R60")
      (value "10k")
      (footprint "eagle-import:R0805")
      (libsource (lib "eagle-import") (part "R-EU_R0805"))
    )
    (comp (ref "R61")
      (value "10k")
      (footprint "eagle-import:R0805")
      (libsource (lib "eagle-import") (part "R-EU_R0805"))
    )
    (comp (ref "R62")
      (value "10k")
      (footprint "eagle-import:R0805")
      (libsource (lib "eagle-import") (part "R-EU_R0805"))
    )
    (comp (ref "R63")
      (value "10k")
      (footprint "eagle-import:R0805")
      (libsource (lib "eagle-import") (part "R-EU_R0805"))
    )
    (comp (ref "R64")
      (value "10k")
      (footprint "eagle-import:R0805")
      (libsource (lib "eagle-import") (part "R-EU_R0805"))
    )
    (comp (ref "R65")
      (value "10k")
      (footprint "eagle-import:R0805")
      (libsource (lib "eagle-import") (part "R-EU_R0805"))
    )
    (comp (ref "R66")
      (value "10k")
      (footprint "eagle-import:R0805")
      (libsource (lib "eagle-import") (part "R-EU_R0805"))
    )
    (comp (ref "R67")
      (value "10k")
      (footprint "eagle-import:R0805")
      (libsource (lib "eagle-import") (part "R-EU_R0805"))
    )
    (comp (ref "R68")
      (value "10k")
      (footprint "eagle-import:R0805")
      (libsource (lib "eagle-import") (part "R-EU_R0805"))
    )
    (comp (ref "R69")
      (value "10k")
      (footprint "eagle-import:R0805")
      (libsource (lib "eagle-import") (part "R-EU_R0805"))
    )
    (comp (ref "R70")
      (value "1k2")
      (footprint "eagle-import:R0805")
      (libsource (lib "eagle-import") (part "R-EU_R0805"))
    )
    (comp (ref "R71")
      (value "49k9")
      (footprint "eagle-import:R0805")
      (libsource (lib "eagle-import") (part "R-EU_R0805"))
    )
    (comp (ref "R72")
      (value "10k")
      (footprint "eagle-import:R0805")
      (libsource (lib "eagle-import") (part "R-EU_R0805"))
    )
    (comp (ref "R73")
      (value "1k2")
      (footprint "eagle-import:R0805")
      (libsource (lib "eagle-import") (part "R-EU_R0805"))
    )
    (comp (ref "R74")
      (value "10k")
      (footprint "eagle-import:R0805")
      (libsource (lib "eagle-import") (part "R-EU_R0805"))
    )
    (comp (ref "R75")
      (value "1k")
      (footprint "eagle-import:R0805")
      (libsource (lib "eagle-import") (part "R-EU_R0805"))
    )
    (comp (ref "R76")
      (value "47R")
      (footprint "eagle-import:R0805")
      (libsource (lib "eagle-import") (part "R-EU_R0805"))
    )
    (comp (ref "R77")
      (value "4k7")
      (footprint "eagle-import:R1206")
      (libsource (lib "eagle-import") (part "R-EU_R1206"))
    )
    (comp (ref "R78")
      (value "10k")
      (footprint "eagle-import:R0805")
      (libsource (lib "eagle-import") (part "R-EU_R0805"))
    )
    (comp (ref "R79")
      (value "1k")
      (footprint "eagle-import:R0805")
      (libsource (lib "eagle-import") (part "R-EU_R0805"))
    )
    (comp (ref "R80")
      (value "4k7")
      (footprint "eagle-import:R1206")
      (libsource (lib "eagle-import") (part "R-EU_R1206"))
    )
    (comp (ref "R81")
      (value "51k")
      (footprint "eagle-import:R0805")
      (libsource (lib "eagle-import") (part "R-EU_R0805"))
    )
    (comp (ref "R82")
      (value "10k")
      (footprint "eagle-import:R0805")
      (libsource (lib "eagle-import") (part "R-EU_R0805"))
    )
    (comp (ref "R83")
      (value "47R")
      (footprint "eagle-import:R0805")
      (libsource (lib "eagle-import") (part "R-EU_R0805"))
    )
    (comp (ref "R84")
      (value "10k")
      (footprint "eagle-import:R0805")
      (libsource (lib "eagle-import") (part "R-EU_R0805"))
    )
    (comp (ref "R85")
      (value "1k")
      (footprint "eagle-import:R0805")
      (libsource (lib "eagle-import") (part "R-EU_R0805"))
    )
    (comp (ref "R86")
      (value "10k")
      (footprint "eagle-import:R0805")
      (libsource (lib "eagle-import") (part "R-EU_R0805"))
    )
    (comp (ref "R87")
      (value "1k")
      (footprint "eagle-import:R0805")
      (libsource (lib "eagle-import") (part "R-EU_R0805"))
    )
    (comp (ref "R88")
      (value "200k")
      (footprint "eagle-import:R0805")
      (libsource (lib "eagle-import") (part "R-EU_R0805"))
    )
    (comp (ref "R89")
      (value "10k")
      (footprint "eagle-import:R0805")
      (libsource (lib "eagle-import") (part "R-EU_R0805"))
    )
    (comp (ref "R90")
      (value "10k")
      (footprint "eagle-import:R0805")
      (libsource (lib "eagle-import") (part "R-EU_R0805"))
    )
    (comp (ref "R91")
      (value "1k")
      (footprint "eagle-import:R0805")
      (libsource (lib "eagle-import") (part "R-EU_R0805"))
    )
    (comp (ref "R92")
      (value "1k")
      (footprint "eagle-import:R0805")
      (libsource (lib "eagle-import") (part "R-EU_R0805"))
    )
    (comp (ref "R93")
      (value "1k")
      (footprint "eagle-import:R0805")
      (libsource (lib "eagle-import") (part "R-EU_R0805"))
    )
    (comp (ref "R94")
      (value "1k")
      (footprint "eagle-import:R0805")
      (libsource (lib "eagle-import") (part "R-EU_R0805"))
    )
    (comp (ref "R95")
      (value "1k")
      (footprint "eagle-import:R0805")
      (libsource (lib "eagle-import") (part "R-EU_R0805"))
    )
    (comp (ref "R96")
      (value "1k")
      (footprint "eagle-import:R0805")
      (libsource (lib "eagle-import") (part "R-EU_R0805"))
    )
    (comp (ref "R97")
      (value "47R")
      (footprint "eagle-import:R0805")
      (libsource (lib "eagle-import") (part "R-EU_R0805"))
    )
    (comp (ref "S1")
      (value "DA06")
      (footprint "eagle-import:DA-06")
      (fields (field (name "MPN") "MCDA06"))
      (libsource (lib "eagle-import") (part "DA06"))
    )
    (comp (ref "U1")
      (value "MCP2515-SO")
      (footprint "eagle-import:SO-18DW")
      (libsource (lib "eagle-import") (part "MCP2515-SO"))
    )
    (comp (ref "U2")
      (value "MCP2562-SN")
      (footprint "eagle-import:SO-08")
      (libsource (lib "eagle-import") (part "MCP2562-SN"))
    )
    (comp (ref "U3")
      (value "74HC4053D")
      (footprint "eagle-import:SO16")
      (libsource (lib "eagle-import") (part "744053D"))
    )
    (comp (ref "U4")
      (value "AVR64DD32-I/PT")
      (footprint "eagle-import:TQFP32-08")
      (libsource (lib "eagle-import") (part "AVR64DD32/32-PT"))
    )
    (comp (ref "U5")
      (value "AT24C256C-SSHL-T")
      (footprint "eagle-import:SO-08")
      (fields (field (name "MPN") "24AA256T-I/SM"))
      (libsource (lib "eagle-import") (part "24SNAA256"))
    )
    (comp (ref "U6")
      (value "AVR64DD32-I/PT")
      (footprint "eagle-import:TQFP32-08")
      (libsource (lib "eagle-import") (part "AVR64DD32/32-PT"))
    )
    (comp (ref "U7")
      (value "74HC4053D")
      (footprint "eagle-import:SO16")
      (libsource (lib "eagle-import") (part "744053D"))
    )
    (comp (ref "U8")
      (value "74AHC1G08DBV")
      (footprint "eagle-import:SOT23-5")
      (libsource (lib "eagle-import") (part "741G08DBVAHC"))
    )
    (comp (ref "U10")
      (value "MCP6002")
      (footprint "eagle-import:SO08")
      (libsource (lib "eagle-import") (part "MCP602SN"))
    )
    (comp (ref "U11")
      (value "UCC27517")
      (footprint "eagle-import:SOT23-5L")
      (libsource (lib "eagle-import") (part "UCC27517"))
    )
    (comp (ref "U12")
      (value "AP2553")
      (footprint "eagle-import:SOT23-6L")
      (libsource (lib "eagle-import") (part "AP2553"))
    )
    (comp (ref "U13")
      (value "CH340N")
      (footprint "eagle-import:SO-08")
      (libsource (lib "eagle-import") (part "CH330N"))
    )
    (comp (ref "U14")
      (value "AP64102")
      (footprint "eagle-import:SO08-EP")
      (libsource (lib "eagle-import") (part "AP64352"))
    )
    (comp (ref "Y1")
      (value "G5320000122080")
      (footprint "eagle-import:CRYSTAL-TXC-7A")
      (libsource (lib "eagle-import") (part "CRYSTALTXC-7A"))
    )
    (comp (ref "Y2")
      (value "G5320000122080")
      (footprint "eagle-import:CRYSTAL-TXC-7A")
      (libsource (lib "eagle-import") (part "CRYSTALTXC-7A"))
    )
  )
  (nets
    (net (code "1") (name "+5V") (class "Default")
      (node (ref "C11") (pin "1") (pinfunction "1_1") (pintype "passive"))
      (node (ref "C17") (pin "1") (pinfunction "1_1") (pintype "passive"))
      (node (ref "C18") (pin "1") (pinfunction "1_1") (pintype "passive"))
      (node (ref "C19") (pin "1") (pinfunction "1_1") (pintype "passive"))
      (node (ref "C21") (pin "1") (pinfunction "1_1") (pintype "passive"))
      (node (ref "C22") (pin "1") (pinfunction "1_1") (pintype "passive"))
      (node (ref "C23") (pin "1") (pinfunction "1_1") (pintype "passive"))
      (node (ref "C24") (pin "1") (pinfunction "1_1") (pintype "passive"))
      (node (ref "C25") (pin "1") (pinfunction "1_1") (pintype "passive"))
      (node (ref "C26") (pin "1") (pinfunction "1_1") (pintype "passive"))
      (node (ref "C27") (pin "1") (pinfunction "1_1") (pintype "passive"))
      (node (ref "C30") (pin "1") (pinfunction "1_1") (pintype "passive"))
      (node (ref "C32") (pin "1") (pinfunction "1_1") (pintype "passive"))
      (node (ref "C4") (pin "1") (pinfunction "1_1") (pintype "passive"))
      (node (ref "C41") (pin "1") (pinfunction "1_1") (pintype "passive"))
      (node (ref "C44") (pin "1") (pinfunction "1_1") (pintype "passive"))
      (node (ref "C46") (pin "1") (pinfunction "1_1") (pintype "passive"))
      (node (ref "C48") (pin "1") (pinfunction "1_1") (pintype "passive"))
      (node (ref "C8") (pin "1") (pinfunction "1_1") (pintype "passive"))
      (node (ref "C9") (pin "1") (pinfunction "1_1") (pintype "passive"))
      (node (ref "D15") (pin "3") (pinfunction "C2_3") (pintype "passive"))
      (node (ref "J7") (pin "1") (pinfunction "S_1") (pintype "passive"))
      (node (ref "JP1") (pin "2") (pinfunction "2_2") (pintype "passive"))
      (node (ref "JP2") (pin "2") (pinfunction "2_2") (pintype "passive"))
      (node (ref "L1") (pin "2") (pinfunction "2_2") (pintype "passive"))
      (node (ref "R1") (pin "2") (pinfunction "2_2") (pintype "passive"))
      (node (ref "R12") (pin "2") (pinfunction "2_2") (pintype "passive"))
      (node (ref "R42") (pin "2") (pinfunction "2_2") (pintype "passive"))
      (node (ref "R43") (pin "2") (pinfunction "2_2") (pintype "passive"))
      (node (ref "R53") (pin "2") (pinfunction "2_2") (pintype "passive"))
      (node (ref "R72") (pin "2") (pinfunction "2_2") (pintype "passive"))
      (node (ref "R81") (pin "2") (pinfunction "2_2") (pintype "passive"))
      (node (ref "U1") (pin "18") (pinfunction "VDD_18") (pintype "bidirectional"))
      (node (ref "U12") (pin "1") (pinfunction "IN_1") (pintype "bidirectional"))
      (node (ref "U2") (pin "3") (pinfunction "VDD_3") (pintype "bidirectional"))
      (node (ref "U2") (pin "5") (pinfunction "VIO_5") (pintype "bidirectional"))
      (node (ref "U3") (pin "16") (pinfunction "VCC_16") (pintype "power_in"))
      (node (ref "U4") (pin "10") (pinfunction "VDDIO2_10") (pintype "bidirectional"))
      (node (ref "U4") (pin "18") (pinfunction "VDD_18") (pintype "bidirectional"))
      (node (ref "U4") (pin "28") (pinfunction "VDD_28") (pintype "bidirectional"))
      (node (ref "U5") (pin "8") (pinfunction "VCC_8") (pintype "power_in"))
      (node (ref "U6") (pin "10") (pinfunction "VDDIO2_10") (pintype "bidirectional"))
      (node (ref "U6") (pin "18") (pinfunction "VDD_18") (pintype "bidirectional"))
      (node (ref "U6") (pin "28") (pinfunction "VDD_28") (pintype "bidirectional"))
      (node (ref "U7") (pin "16") (pinfunction "VCC_16") (pintype "power_in"))
      (node (ref "U8") (pin "5") (pinfunction "VCC_5") (pintype "power_in"))
    )
    (net (code "2") (name "+12V") (class "Default")
      (node (ref "C53") (pin "+") (pinfunction "+_+") (pintype "passive"))
      (node (ref "D16") (pin "2") (pinfunction "C_2") (pintype "passive"))
      (node (ref "D17") (pin "2") (pinfunction "C_2") (pintype "passive"))
      (node (ref "D26") (pin "C") (pinfunction "C_C") (pintype "passive"))
      (node (ref "D28") (pin "3") (pinfunction "C_3") (pintype "passive"))
      (node (ref "D29") (pin "A") (pinfunction "A_A") (pintype "passive"))
      (node (ref "D32") (pin "C") (pinfunction "C_C") (pintype "passive"))
      (node (ref "F1") (pin "2A") (pinfunction "2_2A") (pintype "passive"))
      (node (ref "F1") (pin "2B") (pinfunction "2_2B") (pintype "passive"))
      (node (ref "J12") (pin "1") (pinfunction "1_1") (pintype "passive"))
      (node (ref "J2") (pin "6") (pinfunction "1_6") (pintype "passive"))
      (node (ref "J3") (pin "6") (pinfunction "1_6") (pintype "passive"))
      (node (ref "J4") (pin "6") (pinfunction "1_6") (pintype "passive"))
      (node (ref "K1") (pin "1") (pinfunction "+_1") (pintype "passive"))
      (node (ref "K2") (pin "1") (pinfunction "+_1") (pintype "passive"))
      (node (ref "K3") (pin "S1") (pinfunction "S_S1") (pintype "passive"))
      (node (ref "Q9") (pin "2") (pinfunction "S_2") (pintype "passive"))
      (node (ref "R90") (pin "2") (pinfunction "2_2") (pintype "passive"))
    )
    (net (code "3") (name "/5V_SW") (class "Default")
      (node (ref "C35") (pin "1") (pinfunction "1_1") (pintype "passive"))
      (node (ref "C36") (pin "1") (pinfunction "1_1") (pintype "passive"))
      (node (ref "C39") (pin "1") (pinfunction "1_1") (pintype "passive"))
      (node (ref "C40") (pin "1") (pinfunction "1_1") (pintype "passive"))
      (node (ref "C43") (pin "1") (pinfunction "1_1") (pintype "passive"))
      (node (ref "D25") (pin "4") (pinfunction "C3_4") (pintype "passive"))
      (node (ref "J1") (pin "1") (pinfunction "1_1") (pintype "bidirectional"))
      (node (ref "J1") (pin "2") (pinfunction "2_2") (pintype "bidirectional"))
      (node (ref "J11") (pin "1") (pinfunction "1_1") (pintype "passive"))
      (node (ref "R20") (pin "2") (pinfunction "2_2") (pintype "passive"))
      (node (ref "R21") (pin "2") (pinfunction "2_2") (pintype "passive"))
      (node (ref "U10") (pin "8") (pinfunction "V+_8") (pintype "power_in"))
      (node (ref "U11") (pin "1") (pinfunction "VDD_1") (pintype "bidirectional"))
      (node (ref "U12") (pin "6") (pinfunction "OUT_6") (pintype "bidirectional"))
    )
    (net (code "4") (name "/20MHZ") (class "Default")
      (node (ref "R46") (pin "2") (pinfunction "2_2") (pintype "passive"))
      (node (ref "U1") (pin "3") (pinfunction "CLKOUT/SOF_3") (pintype "bidirectional"))
    )
    (net (code "5") (name "/AC_DETECT") (class "Default")
      (node (ref "J4") (pin "4") (pinfunction "1_4") (pintype "passive"))
      (node (ref "R8") (pin "1") (pinfunction "1_1") (pintype "passive"))
    )
    (net (code "6") (name "/AN_OUT") (class "Default")
      (node (ref "D22") (pin "3") (pinfunction "C_3") (pintype "passive"))
      (node (ref "J9") (pin "1") (pinfunction "1_1") (pintype "passive"))
      (node (ref "R76") (pin "2") (pinfunction "2_2") (pintype "passive"))
      (node (ref "R97") (pin "2") (pinfunction "2_2") (pintype "passive"))
    )
    (net (code "7") (name "/CANH") (class "Default")
      (node (ref "D1") (pin "2") (pinfunction "K2_2") (pintype "passive"))
      (node (ref "J5") (pin "1L") (pinfunction "L1_1L") (pintype "bidirectional"))
      (node (ref "J5") (pin "1R") (pinfunction "R1_1R") (pintype "bidirectional"))
      (node (ref "S1") (pin "6") (pinfunction "6_6") (pintype "passive"))
      (node (ref "U2") (pin "7") (pinfunction "CANH_7") (pintype "bidirectional"))
    )
    (net (code "8") (name "/CANL") (class "Default")
      (node (ref "D1") (pin "1") (pinfunction "K1_1") (pintype "passive"))
      (node (ref "J5") (pin "2L") (pinfunction "L2_2L") (pintype "bidirectional"))
      (node (ref "J5") (pin "2R") (pinfunction "R2_2R") (pintype "bidirectional"))
      (node (ref "R51") (pin "2") (pinfunction "2_2") (pintype "passive"))
      (node (ref "U2") (pin "6") (pinfunction "CANL_6") (pintype "bidirectional"))
    )
    (net (code "9") (name "/CONT+") (class "Default")
      (node (ref "D27") (pin "C") (pinfunction "C_C") (pintype "passive"))
      (node (ref "J13") (pin "3") (pinfunction "1_3") (pintype "passive"))
      (node (ref "J13") (pin "4") (pinfunction "1_4") (pintype "passive"))
      (node (ref "K3") (pin "S2") (pinfunction "S_S2") (pintype "passive"))
    )
    (net (code "10") (name "/CONT-") (class "Default")
      (node (ref "D26") (pin "A") (pinfunction "A_A") (pintype "passive"))
      (node (ref "D27") (pin "A") (pinfunction "A_A") (pintype "passive"))
      (node (ref "J13") (pin "2") (pinfunction "1_2") (pintype "passive"))
      (node (ref "Q8") (pin "4") (pinfunction "D_4") (pintype "passive"))
      (node (ref "R77") (pin "1") (pinfunction "1_1") (pintype "passive"))
    )
    (net (code "11") (name "/CONT_MON") (class "Default")
      (node (ref "C33") (pin "1") (pinfunction "1_1") (pintype "passive"))
      (node (ref "R94") (pin "2") (pinfunction "2_2") (pintype "passive"))
      (node (ref "U4") (pin "22") (pinfunction "PF2_22") (pintype "bidirectional"))
    )
    (net (code "12") (name "/CONT_PWM") (class "Default")
      (node (ref "R78") (pin "2") (pinfunction "2_2") (pintype "passive"))
      (node (ref "U11") (pin "3") (pinfunction "IN+_3") (pintype "bidirectional"))
      (node (ref "U6") (pin "14") (pinfunction "PD4_14") (pintype "bidirectional"))
    )
    (net (code "13") (name "/CONT_RLY1") (class "Default")
      (node (ref "R47") (pin "2") (pinfunction "2_2") (pintype "passive"))
      (node (ref "U6") (pin "12") (pinfunction "PD2_12") (pintype "bidirectional"))
      (node (ref "U8") (pin "2") (pinfunction "I1_2") (pintype "input"))
    )
    (net (code "14") (name "/CONT_RLY2") (class "Default")
      (node (ref "R52") (pin "2") (pinfunction "2_2") (pintype "passive"))
      (node (ref "U4") (pin "23") (pinfunction "PF3_23") (pintype "bidirectional"))
      (node (ref "U8") (pin "1") (pinfunction "I0_1") (pintype "input"))
    )
    (net (code "15") (name "/CURR_REF") (class "Default")
      (node (ref "C52") (pin "1") (pinfunction "1_1") (pintype "passive"))
      (node (ref "R91") (pin "2") (pinfunction "2_2") (pintype "passive"))
      (node (ref "U4") (pin "20") (pinfunction "PF0/XTAL32K1_20") (pintype "bidirectional"))
    )
    (net (code "16") (name "/CURR_VOUT") (class "Default")
      (node (ref "C45") (pin "1") (pinfunction "1_1") (pintype "passive"))
      (node (ref "R85") (pin "2") (pinfunction "2_2") (pintype "passive"))
      (node (ref "U4") (pin "17") (pinfunction "PD7_17") (pintype "bidirectional"))
    )
    (net (code "17") (name "/DAC_OUT") (class "Default")
      (node (ref "R96") (pin "1") (pinfunction "1_1") (pintype "passive"))
      (node (ref "U4") (pin "16") (pinfunction "PD6_16") (pintype "bidirectional"))
    )
    (net (code "18") (name "/DC_PRES") (class "Default")
      (node (ref "J3") (pin "2") (pinfunction "1_2") (pintype "passive"))
      (node (ref "R6") (pin "1") (pinfunction "1_1") (pintype "passive"))
    )
    (net (code "19") (name "/DIP1") (class "Default")
      (node (ref "R67") (pin "1") (pinfunction "1_1") (pintype "passive"))
      (node (ref "R68") (pin "2") (pinfunction "2_2") (pintype "passive"))
      (node (ref "R74") (pin "2") (pinfunction "2_2") (pintype "passive"))
      (node (ref "U6") (pin "22") (pinfunction "PF2_22") (pintype "bidirectional"))
    )
    (net (code "20") (name "/DIP2") (class "Default")
      (node (ref "R58") (pin "2") (pinfunction "2_2") (pintype "passive"))
      (node (ref "R61") (pin "1") (pinfunction "1_1") (pintype "passive"))
      (node (ref "R62") (pin "2") (pinfunction "2_2") (pintype "passive"))
      (node (ref "U6") (pin "24") (pinfunction "PF4_24") (pintype "bidirectional"))
    )
    (net (code "21") (name "/DIP_RD") (class "Default")
      (node (ref "R61") (pin "2") (pinfunction "2_2") (pintype "passive"))
      (node (ref "R67") (pin "2") (pinfunction "2_2") (pintype "passive"))
      (node (ref "U6") (pin "23") (pinfunction "PF3_23") (pintype "bidirectional"))
    )
    (net (code "22") (name "/ESTOP") (class "Default")
      (node (ref "D21") (pin "3") (pinfunction "C_3") (pintype "passive"))
      (node (ref "D30") (pin "C") (pinfunction "C_C") (pintype "passive"))
      (node (ref "J12") (pin "2") (pinfunction "1_2") (pintype "passive"))
      (node (ref "K3") (pin "1") (pinfunction "1_1") (pintype "passive"))
      (node (ref "Q7") (pin "2") (pinfunction "S_2") (pintype "passive"))
      (node (ref "R66") (pin "2") (pinfunction "2_2") (pintype "passive"))
    )
    (net (code "23") (name "/ESTOP_IN") (class "Default")
      (node (ref "J3") (pin "5") (pinfunction "1_5") (pintype "passive"))
      (node (ref "R3") (pin "1") (pinfunction "1_1") (pintype "passive"))
    )
    (net (code "24") (name "/ESTOP_MON") (class "Default")
      (node (ref "C29") (pin "1") (pinfunction "1_1") (pintype "passive"))
      (node (ref "R50") (pin "2") (pinfunction "2_2") (pintype "passive"))
      (node (ref "U4") (pin "24") (pinfunction "PF4_24") (pintype "bidirectional"))
    )
    (net (code "25") (name "/IN1_MCU") (class "Default")
      (node (ref "C13") (pin "1") (pinfunction "1_1") (pintype "passive"))
      (node (ref "R26") (pin "2") (pinfunction "2_2") (pintype "passive"))
      (node (ref "U4") (pin "8") (pinfunction "PC2_8") (pintype "bidirectional"))
    )
    (net (code "26") (name "/IN2_MCU") (class "Default")
      (node (ref "C14") (pin "1") (pinfunction "1_1") (pintype "passive"))
      (node (ref "R28") (pin "2") (pinfunction "2_2") (pintype "passive"))
      (node (ref "U4") (pin "7") (pinfunction "PC1_7") (pintype "bidirectional"))
    )
    (net (code "27") (name "/IN3_MCU") (class "Default")
      (node (ref "C15") (pin "1") (pinfunction "1_1") (pintype "passive"))
      (node (ref "R29") (pin "2") (pinfunction "2_2") (pintype "passive"))
      (node (ref "U4") (pin "6") (pinfunction "PC0_6") (pintype "bidirectional"))
    )
    (net (code "28") (name "/IN4_MCU") (class "Default")
      (node (ref "C16") (pin "1") (pinfunction "1_1") (pintype "passive"))
      (node (ref "R32") (pin "2") (pinfunction "2_2") (pintype "passive"))
      (node (ref "U4") (pin "5") (pinfunction "PA7_5") (pintype "bidirectional"))
    )
    (net (code "29") (name "/IN5_MCU") (class "Default")
      (node (ref "C6") (pin "1") (pinfunction "1_1") (pintype "passive"))
      (node (ref "R23") (pin "2") (pinfunction "2_2") (pintype "passive"))
      (node (ref "U4") (pin "4") (pinfunction "PA6_4") (pintype "bidirectional"))
    )
    (net (code "30") (name "/IN6_MCU") (class "Default")
      (node (ref "C12") (pin "1") (pinfunction "1_1") (pintype "passive"))
      (node (ref "R24") (pin "2") (pinfunction "2_2") (pintype "passive"))
      (node (ref "U4") (pin "3") (pinfunction "PA5_3") (pintype "bidirectional"))
    )
    (net (code "31") (name "/IN7_MCU") (class "Default")
      (node (ref "C3") (pin "1") (pinfunction "1_1") (pintype "passive"))
      (node (ref "R14") (pin "2") (pinfunction "2_2") (pintype "passive"))
      (node (ref "U4") (pin "2") (pinfunction "PA4_2") (pintype "bidirectional"))
    )
    (net (code "32") (name "/IN8_MCU") (class "Default")
      (node (ref "C5") (pin "1") (pinfunction "1_1") (pintype "passive"))
      (node (ref "R18") (pin "2") (pinfunction "2_2") (pintype "passive"))
      (node (ref "U4") (pin "1") (pinfunction "PA3_1") (pintype "bidirectional"))
    )
    (net (code "33") (name "/KEY_IGN") (class "Default")
      (node (ref "J4") (pin "5") (pinfunction "1_5") (pintype "passive"))
      (node (ref "R7") (pin "1") (pinfunction "1_1") (pintype "passive"))
    )
    (net (code "34") (name "/KEY_START") (class "Default")
      (node (ref "J3") (pin "4") (pinfunction "1_4") (pintype "passive"))
      (node (ref "R4") (pin "1") (pinfunction "1_1") (pintype "passive"))
    )
    (net (code "35") (name "/LED1") (class "Default")
      (node (ref "R93") (pin "2") (pinfunction "2_2") (pintype "passive"))
      (node (ref "U6") (pin "17") (pinfunction "PD7_17") (pintype "bidirectional"))
    )
    (net (code "36") (name "/LED2") (class "Default")
      (node (ref "R92") (pin "2") (pinfunction "2_2") (pintype "passive"))
      (node (ref "U6") (pin "21") (pinfunction "PF1/XTAL32K2_21") (pintype "bidirectional"))
    )
    (net (code "37") (name "/MISO") (class "Default")
      (node (ref "U1") (pin "15") (pinfunction "SO_15") (pintype "bidirectional"))
      (node (ref "U6") (pin "3") (pinfunction "PA5_3") (pintype "bidirectional"))
    )
    (net (code "38") (name "/MOSI") (class "Default")
      (node (ref "U1") (pin "14") (pinfunction "SI_14") (pintype "bidirectional"))
      (node (ref "U6") (pin "2") (pinfunction "PA4_2") (pintype "bidirectional"))
    )
    (net (code "39") (name "/OUT1") (class "Default")
      (node (ref "R37") (pin "1") (pinfunction "1_1") (pintype "passive"))
      (node (ref "R38") (pin "2") (pinfunction "2_2") (pintype "passive"))
      (node (ref "U4") (pin "13") (pinfunction "PD3_13") (pintype "bidirectional"))
    )
    (net (code "40") (name "/OUT2") (class "Default")
      (node (ref "R35") (pin "1") (pinfunction "1_1") (pintype "passive"))
      (node (ref "R39") (pin "2") (pinfunction "2_2") (pintype "passive"))
      (node (ref "U4") (pin "12") (pinfunction "PD2_12") (pintype "bidirectional"))
    )
    (net (code "41") (name "/OUT3") (class "Default")
      (node (ref "R34") (pin "2") (pinfunction "2_2") (pintype "passive"))
      (node (ref "R36") (pin "1") (pinfunction "1_1") (pintype "passive"))
      (node (ref "U4") (pin "11") (pinfunction "PD1_11") (pintype "bidirectional"))
    )
    (net (code "42") (name "/OUT4") (class "Default")
      (node (ref "R16") (pin "2") (pinfunction "2_2") (pintype "passive"))
      (node (ref "R22") (pin "1") (pinfunction "1_1") (pintype "passive"))
      (node (ref "U4") (pin "9") (pinfunction "PC3_9") (pintype "bidirectional"))
    )
    (net (code "43") (name "/PC_RX") (class "Default")
      (node (ref "U3") (pin "15") (pinfunction "2Z_15") (pintype "input"))
      (node (ref "U6") (pin "1") (pinfunction "PA3_1") (pintype "bidirectional"))
    )
    (net (code "44") (name "/PC_TX") (class "Default")
      (node (ref "U3") (pin "4") (pinfunction "3Z_4") (pintype "input"))
      (node (ref "U6") (pin "32") (pinfunction "PA2_32") (pintype "bidirectional"))
    )
    (net (code "45") (name "/PRECHG") (class "Default")
      (node (ref "R86") (pin "2") (pinfunction "2_2") (pintype "passive"))
      (node (ref "R87") (pin "1") (pinfunction "1_1") (pintype "passive"))
      (node (ref "U6") (pin "13") (pinfunction "PD3_13") (pintype "bidirectional"))
    )
    (net (code "46") (name "/PRECHG_FB") (class "Default")
      (node (ref "J3") (pin "3") (pinfunction "1_3") (pintype "passive"))
      (node (ref "R5") (pin "1") (pinfunction "1_1") (pintype "passive"))
    )
    (net (code "47") (name "/PWR_EN") (class "Default")
      (node (ref "Q10") (pin "1") (pinfunction "G_1") (pintype "passive"))
      (node (ref "Q6") (pin "1") (pinfunction "G_1") (pintype "passive"))
      (node (ref "R59") (pin "2") (pinfunction "2_2") (pintype "passive"))
      (node (ref "U12") (pin "3") (pinfunction "EN_3") (pintype "bidirectional"))
      (node (ref "U6") (pin "16") (pinfunction "PD6_16") (pintype "bidirectional"))
    )
    (net (code "48") (name "/RLY1") (class "Default")
      (node (ref "R40") (pin "1") (pinfunction "1_1") (pintype "passive"))
      (node (ref "R41") (pin "2") (pinfunction "2_2") (pintype "passive"))
      (node (ref "U4") (pin "14") (pinfunction "PD4_14") (pintype "bidirectional"))
    )
    (net (code "49") (name "/RLY2") (class "Default")
      (node (ref "R44") (pin "1") (pinfunction "1_1") (pintype "passive"))
      (node (ref "R45") (pin "2") (pinfunction "2_2") (pintype "passive"))
      (node (ref "U4") (pin "15") (pinfunction "PD5_15") (pintype "bidirectional"))
    )
    (net (code "50") (name "/SCK") (class "Default")
      (node (ref "U1") (pin "13") (pinfunction "SCK_13") (pintype "bidirectional"))
      (node (ref "U6") (pin "4") (pinfunction "PA6_4") (pintype "bidirectional"))
    )
    (net (code "51") (name "/SCL") (class "Default")
      (node (ref "R43") (pin "1") (pinfunction "1_1") (pintype "passive"))
      (node (ref "U4") (pin "31") (pinfunction "PA1/XTALHF2_31") (pintype "bidirectional"))
      (node (ref "U5") (pin "6") (pinfunction "SCL_6") (pintype "input"))
      (node (ref "U6") (pin "9") (pinfunction "PC3_9") (pintype "bidirectional"))
    )
    (net (code "52") (name "/SDA") (class "Default")
      (node (ref "R42") (pin "1") (pinfunction "1_1") (pintype "passive"))
      (node (ref "U4") (pin "30") (pinfunction "PA0/XTALHF1_30") (pintype "bidirectional"))
      (node (ref "U5") (pin "5") (pinfunction "SDA_5") (pintype "bidirectional"))
      (node (ref "U6") (pin "8") (pinfunction "PC2_8") (pintype "bidirectional"))
    )
    (net (code "53") (name "/TTL_RX") (class "Default")
      (node (ref "D15") (pin "4") (pinfunction "C3_4") (pintype "passive"))
      (node (ref "J7") (pin "2") (pinfunction "S_2") (pintype "passive"))
      (node (ref "U3") (pin "2") (pinfunction "2Y0_2") (pintype "bidirectional"))
    )
    (net (code "54") (name "/TTL_TX") (class "Default")
      (node (ref "D15") (pin "2") (pinfunction "C1_2") (pintype "passive"))
      (node (ref "J7") (pin "3") (pinfunction "S_3") (pintype "passive"))
      (node (ref "U3") (pin "5") (pinfunction "3Y0_5") (pintype "bidirectional"))
    )
    (net (code "55") (name "/UD+") (class "Default")
      (node (ref "D24") (pin "3") (pinfunction "C2_3") (pintype "passive"))
      (node (ref "J10") (pin "3") (pinfunction "3_3") (pintype "passive"))
      (node (ref "U13") (pin "1") (pinfunction "UD+_1") (pintype "bidirectional"))
    )
    (net (code "56") (name "/UD-") (class "Default")
      (node (ref "D24") (pin "2") (pinfunction "C1_2") (pintype "passive"))
      (node (ref "J10") (pin "2") (pinfunction "2_2") (pintype "passive"))
      (node (ref "U13") (pin "2") (pinfunction "UD-_2") (pintype "bidirectional"))
    )
    (net (code "57") (name "/UPDI") (class "Default")
      (node (ref "R57") (pin "1") (pinfunction "1_1") (pintype "passive"))
      (node (ref "U7") (pin "2") (pinfunction "2Y0_2") (pintype "bidirectional"))
      (node (ref "U7") (pin "4") (pinfunction "3Z_4") (pintype "input"))
    )
    (net (code "58") (name "/UPDI1") (class "Default")
      (node (ref "JP2") (pin "4") (pinfunction "4_4") (pintype "passive"))
      (node (ref "U6") (pin "27") (pinfunction "PF7/UPDI_27") (pintype "bidirectional"))
      (node (ref "U7") (pin "5") (pinfunction "3Y0_5") (pintype "bidirectional"))
    )
    (net (code "59") (name "/UPDI2") (class "Default")
      (node (ref "JP1") (pin "4") (pinfunction "4_4") (pintype "passive"))
      (node (ref "U4") (pin "27") (pinfunction "PF7/UPDI_27") (pintype "bidirectional"))
      (node (ref "U7") (pin "3") (pinfunction "3Y1_3") (pintype "bidirectional"))
    )
    (net (code "60") (name "/UPDISEL") (class "Default")
      (node (ref "R65") (pin "1") (pinfunction "1_1") (pintype "passive"))
      (node (ref "U13") (pin "4") (pinfunction "~{RTS}_4") (pintype "bidirectional"))
      (node (ref "U7") (pin "9") (pinfunction "S3_9") (pintype "bidirectional"))
    )
    (net (code "61") (name "/V_SUPPLY") (class "Default")
      (node (ref "C31") (pin "1") (pinfunction "1_1") (pintype "passive"))
      (node (ref "R95") (pin "2") (pinfunction "2_2") (pintype "passive"))
      (node (ref "U4") (pin "21") (pinfunction "PF1/XTAL32K2_21") (pintype "bidirectional"))
    )
    (net (code "62") (name "/~{5V_FLT}") (class "Default")
      (node (ref "R72") (pin "1") (pinfunction "1_1") (pintype "passive"))
      (node (ref "U12") (pin "4") (pinfunction "FLG_4") (pintype "bidirectional"))
      (node (ref "U6") (pin "15") (pinfunction "PD5_15") (pintype "bidirectional"))
    )
    (net (code "63") (name "/~{BATT_FAULT}") (class "Default")
      (node (ref "C10") (pin "1") (pinfunction "1_1") (pintype "passive"))
      (node (ref "R11") (pin "2") (pinfunction "2_2") (pintype "passive"))
      (node (ref "U4") (pin "32") (pinfunction "PA2_32") (pintype "bidirectional"))
    )
    (net (code "64") (name "/~{BATT_RX}") (class "Default")
      (node (ref "C7") (pin "1") (pinfunction "1_1") (pintype "passive"))
      (node (ref "R19") (pin "2") (pinfunction "2_2") (pintype "passive"))
      (node (ref "U6") (pin "7") (pinfunction "PC1_7") (pintype "bidirectional"))
    )
    (net (code "65") (name "/~{BATT_TX}") (class "Default")
      (node (ref "R13") (pin "2") (pinfunction "2_2") (pintype "passive"))
      (node (ref "U6") (pin "6") (pinfunction "PC0_6") (pintype "bidirectional"))
    )
    (net (code "66") (name "/~{BOOT}") (class "Default")
      (node (ref "R53") (pin "1") (pinfunction "1_1") (pintype "passive"))
      (node (ref "S1") (pin "8") (pinfunction "8_8") (pintype "passive"))
      (node (ref "U6") (pin "25") (pinfunction "PF5_25") (pintype "bidirectional"))
      (node (ref "U7") (pin "10") (pinfunction "S2_10") (pintype "bidirectional"))
      (node (ref "U7") (pin "11") (pinfunction "S1_11") (pintype "bidirectional"))
    )
    (net (code "67") (name "/~{CS_CAN}") (class "Default")
      (node (ref "R1") (pin "1") (pinfunction "1_1") (pintype "passive"))
      (node (ref "U1") (pin "16") (pinfunction "~{CS}_16") (pintype "bidirectional"))
      (node (ref "U6") (pin "5") (pinfunction "PA7_5") (pintype "bidirectional"))
    )
    (net (code "68") (name "/~{IRQ_CAN}") (class "Default")
      (node (ref "U1") (pin "12") (pinfunction "~{INT}_12") (pintype "bidirectional"))
      (node (ref "U6") (pin "20") (pinfunction "PF0/XTAL32K1_20") (pintype "bidirectional"))
    )
    (net (code "69") (name "/~{IRQ}") (class "Default")
      (node (ref "U4") (pin "25") (pinfunction "PF5_25") (pintype "bidirectional"))
      (node (ref "U6") (pin "11") (pinfunction "PD1_11") (pintype "bidirectional"))
    )
    (net (code "70") (name "/~{RST2}") (class "Default")
      (node (ref "JP1") (pin "1") (pinfunction "1_1") (pintype "passive"))
      (node (ref "U4") (pin "26") (pinfunction "PF6/~{RESET}_26") (pintype "bidirectional"))
    )
    (net (code "71") (name "/~{RST}") (class "Default")
      (node (ref "JP2") (pin "1") (pinfunction "1_1") (pintype "passive"))
      (node (ref "U6") (pin "26") (pinfunction "PF6/~{RESET}_26") (pintype "bidirectional"))
    )
    (net (code "72") (name "GND") (class "Default")
      (node (ref "C1") (pin "2") (pinfunction "2_2") (pintype "passive"))
      (node (ref "C10") (pin "2") (pinfunction "2_2") (pintype "passive"))
      (node (ref "C11") (pin "2") (pinfunction "2_2") (pintype "passive"))
      (node (ref "C12") (pin "2") (pinfunction "2_2") (pintype "passive"))
      (node (ref "C13") (pin "2") (pinfunction "2_2") (pintype "passive"))
      (node (ref "C14") (pin "2") (pinfunction "2_2") (pintype "passive"))
      (node (ref "C15") (pin "2") (pinfunction "2_2") (pintype "passive"))
      (node (ref "C16") (pin "2") (pinfunction "2_2") (pintype "passive"))
      (node (ref "C17") (pin "2") (pinfunction "2_2") (pintype "passive"))
      (node (ref "C18") (pin "2") (pinfunction "2_2") (pintype "passive"))
      (node (ref "C19") (pin "2") (pinfunction "2_2") (pintype "passive"))
      (node (ref "C2") (pin "2") (pinfunction "2_2") (pintype "passive"))
      (node (ref "C20") (pin "2") (pinfunction "2_2") (pintype "passive"))
      (node (ref "C21") (pin "2") (pinfunction "2_2") (pintype "passive"))
      (node (ref "C22") (pin "2") (pinfunction "2_2") (pintype "passive"))
      (node (ref "C23") (pin "2") (pinfunction "2_2") (pintype "passive"))
      (node (ref "C24") (pin "2") (pinfunction "2_2") (pintype "passive"))
      (node (ref "C25") (pin "2") (pinfunction "2_2") (pintype "passive"))
      (node (ref "C26") (pin "2") (pinfunction "2_2") (pintype "passive"))
      (node (ref "C27") (pin "2") (pinfunction "2_2") (pintype "passive"))
      (node (ref "C28") (pin "2") (pinfunction "2_2") (pintype "passive"))
      (node (ref "C29") (pin "2") (pinfunction "2_2") (pintype "passive"))
      (node (ref "C3") (pin "2") (pinfunction "2_2") (pintype "passive"))
      (node (ref "C30") (pin "2") (pinfunction "2_2") (pintype "passive"))
      (node (ref "C31") (pin "2") (pinfunction "2_2") (pintype "passive"))
      (node (ref "C32") (pin "2") (pinfunction "2_2") (pintype "passive"))
      (node (ref "C33") (pin "2") (pinfunction "2_2") (pintype "passive"))
      (node (ref "C34") (pin "2") (pinfunction "2_2") (pintype "passive"))
      (node (ref "C35") (pin "2") (pinfunction "2_2") (pintype "passive"))
      (node (ref "C36") (pin "2") (pinfunction "2_2") (pintype "passive"))
      (node (ref "C37") (pin "2") (pinfunction "2_2") (pintype "passive"))
      (node (ref "C38") (pin "2") (pinfunction "2_2") (pintype "passive"))
      (node (ref "C39") (pin "2") (pinfunction "2_2") (pintype "passive"))
      (node (ref "C4") (pin "2") (pinfunction "2_2") (pintype "passive"))
      (node (ref "C40") (pin "2") (pinfunction "2_2") (pintype "passive"))
      (node (ref "C41") (pin "2") (pinfunction "2_2") (pintype "passive"))
      (node (ref "C42") (pin "2") (pinfunction "2_2") (pintype "passive"))
      (node (ref "C43") (pin "2") (pinfunction "2_2") (pintype "passive"))
      (node (ref "C44") (pin "2") (pinfunction "2_2") (pintype "passive"))
      (node (ref "C45") (pin "2") (pinfunction "2_2") (pintype "passive"))
      (node (ref "C46") (pin "2") (pinfunction "2_2") (pintype "passive"))
      (node (ref "C47") (pin "-") (pinfunction "-_-") (pintype "passive"))
      (node (ref "C48") (pin "2") (pinfunction "2_2") (pintype "passive"))
      (node (ref "C5") (pin "2") (pinfunction "2_2") (pintype "passive"))
      (node (ref "C50") (pin "2") (pinfunction "2_2") (pintype "passive"))
      (node (ref "C51") (pin "2") (pinfunction "2_2") (pintype "passive"))
      (node (ref "C52") (pin "2") (pinfunction "2_2") (pintype "passive"))
      (node (ref "C53") (pin "-") (pinfunction "-_-") (pintype "passive"))
      (node (ref "C6") (pin "2") (pinfunction "2_2") (pintype "passive"))
      (node (ref "C7") (pin "2") (pinfunction "2_2") (pintype "passive"))
      (node (ref "C8") (pin "2") (pinfunction "2_2") (pintype "passive"))
      (node (ref "C9") (pin "2") (pinfunction "2_2") (pintype "passive"))
      (node (ref "D1") (pin "3") (pinfunction "A_3") (pintype "passive"))
      (node (ref "D10") (pin "1") (pinfunction "A_1") (pintype "passive"))
      (node (ref "D11") (pin "1") (pinfunction "A_1") (pintype "passive"))
      (node (ref "D12") (pin "1") (pinfunction "A_1") (pintype "passive"))
      (node (ref "D13") (pin "1") (pinfunction "A_1") (pintype "passive"))
      (node (ref "D14") (pin "1") (pinfunction "A_1") (pintype "passive"))
      (node (ref "D15") (pin "1") (pinfunction "A_1") (pintype "passive"))
      (node (ref "D18") (pin "1") (pinfunction "A_1") (pintype "passive"))
      (node (ref "D19") (pin "A") (pinfunction "A_A") (pintype "passive"))
      (node (ref "D2") (pin "A") (pinfunction "A_A") (pintype "passive"))
      (node (ref "D20") (pin "1") (pinfunction "A_1") (pintype "passive"))
      (node (ref "D22") (pin "1") (pinfunction "A_1") (pintype "passive"))
      (node (ref "D23") (pin "1") (pinfunction "A_1") (pintype "passive"))
      (node (ref "D24") (pin "1") (pinfunction "A_1") (pintype "passive"))
      (node (ref "D25") (pin "1") (pinfunction "A_1") (pintype "passive"))
      (node (ref "D3") (pin "A") (pinfunction "A_A") (pintype "passive"))
      (node (ref "D30") (pin "A") (pinfunction "A_A") (pintype "passive"))
      (node (ref "D31") (pin "A") (pinfunction "A_A") (pintype "passive"))
      (node (ref "D32") (pin "A") (pinfunction "A_A") (pintype "passive"))
      (node (ref "D4") (pin "A") (pinfunction "A_A") (pintype "passive"))
      (node (ref "D5") (pin "A") (pinfunction "A_A") (pintype "passive"))
      (node (ref "D6") (pin "1") (pinfunction "A_1") (pintype "passive"))
      (node (ref "D7") (pin "1") (pinfunction "A_1") (pintype "passive"))
      (node (ref "D8") (pin "1") (pinfunction "A_1") (pintype "passive"))
      (node (ref "D9") (pin "1") (pinfunction "A_1") (pintype "passive"))
      (node (ref "J1") (pin "3") (pinfunction "3_3") (pintype "bidirectional"))
      (node (ref "J1") (pin "5") (pinfunction "5_5") (pintype "bidirectional"))
      (node (ref "J1") (pin "7") (pinfunction "7_7") (pintype "bidirectional"))
      (node (ref "J1") (pin "S1") (pinfunction "SHIELD_S1") (pintype "bidirectional"))
      (node (ref "J1") (pin "S2") (pinfunction "SHIELD_S2") (pintype "bidirectional"))
      (node (ref "J10") (pin "4") (pinfunction "4_4") (pintype "passive"))
      (node (ref "J10") (pin "M1") (pinfunction "S1_M1") (pintype "passive"))
      (node (ref "J10") (pin "M2") (pinfunction "S2_M2") (pintype "passive"))
      (node (ref "J11") (pin "2") (pinfunction "1_2") (pintype "passive"))
      (node (ref "J14") (pin "2") (pinfunction "1_2") (pintype "passive"))
      (node (ref "J2") (pin "1") (pinfunction "1_1") (pintype "passive"))
      (node (ref "J3") (pin "1") (pinfunction "1_1") (pintype "passive"))
      (node (ref "J4") (pin "1") (pinfunction "1_1") (pintype "passive"))
      (node (ref "J5") (pin "3L") (pinfunction "L3_3L") (pintype "bidirectional"))
      (node (ref "J5") (pin "3R") (pinfunction "R3_3R") (pintype "bidirectional"))
      (node (ref "J5") (pin "6L") (pinfunction "L6_6L") (pintype "bidirectional"))
      (node (ref "J5") (pin "6R") (pinfunction "R6_6R") (pintype "bidirectional"))
      (node (ref "J5") (pin "7L") (pinfunction "L7_7L") (pintype "bidirectional"))
      (node (ref "J5") (pin "7R") (pinfunction "R7_7R") (pintype "bidirectional"))
      (node (ref "J5") (pin "S1") (pinfunction "SHIELD_S1") (pintype "bidirectional"))
      (node (ref "J5") (pin "S2") (pinfunction "SHIELD_S2") (pintype "bidirectional"))
      (node (ref "J7") (pin "4") (pinfunction "S_4") (pintype "passive"))
      (node (ref "J9") (pin "2") (pinfunction "1_2") (pintype "passive"))
      (node (ref "JP1") (pin "3") (pinfunction "3_3") (pintype "passive"))
      (node (ref "JP2") (pin "3") (pinfunction "3_3") (pintype "passive"))
      (node (ref "LED1") (pin "2") (pinfunction "C_2") (pintype "passive"))
      (node (ref "Q1") (pin "1") (pinfunction "S_1") (pintype "passive"))
      (node (ref "Q1") (pin "3") (pinfunction "S_3") (pintype "passive"))
      (node (ref "Q10") (pin "2") (pinfunction "S_2") (pintype "passive"))
      (node (ref "Q11") (pin "3") (pinfunction "S_3") (pintype "passive"))
      (node (ref "Q2") (pin "1") (pinfunction "S_1") (pintype "passive"))
      (node (ref "Q2") (pin "3") (pinfunction "S_3") (pintype "passive"))
      (node (ref "Q3") (pin "2") (pinfunction "S_2") (pintype "passive"))
      (node (ref "Q4") (pin "2") (pinfunction "S_2") (pintype "passive"))
      (node (ref "Q5") (pin "2") (pinfunction "S_2") (pintype "passive"))
      (node (ref "Q6") (pin "2") (pinfunction "S_2") (pintype "passive"))
      (node (ref "Q8") (pin "3") (pinfunction "S_3") (pintype "passive"))
      (node (ref "R15") (pin "1") (pinfunction "1_1") (pintype "passive"))
      (node (ref "R16") (pin "1") (pinfunction "1_1") (pintype "passive"))
      (node (ref "R17") (pin "1") (pinfunction "1_1") (pintype "passive"))
      (node (ref "R2") (pin "1") (pinfunction "1_1") (pintype "passive"))
      (node (ref "R25") (pin "1") (pinfunction "1_1") (pintype "passive"))
      (node (ref "R27") (pin "1") (pinfunction "1_1") (pintype "passive"))
      (node (ref "R30") (pin "1") (pinfunction "1_1") (pintype "passive"))
      (node (ref "R31") (pin "1") (pinfunction "1_1") (pintype "passive"))
      (node (ref "R33") (pin "1") (pinfunction "1_1") (pintype "passive"))
      (node (ref "R34") (pin "1") (pinfunction "1_1") (pintype "passive"))
      (node (ref "R38") (pin "1") (pinfunction "1_1") (pintype "passive"))
      (node (ref "R39") (pin "1") (pinfunction "1_1") (pintype "passive"))
      (node (ref "R41") (pin "1") (pinfunction "1_1") (pintype "passive"))
      (node (ref "R45") (pin "1") (pinfunction "1_1") (pintype "passive"))
      (node (ref "R47") (pin "1") (pinfunction "1_1") (pintype "passive"))
      (node (ref "R48") (pin "1") (pinfunction "1_1") (pintype "passive"))
      (node (ref "R52") (pin "1") (pinfunction "1_1") (pintype "passive"))
      (node (ref "R55") (pin "1") (pinfunction "1_1") (pintype "passive"))
      (node (ref "R59") (pin "1") (pinfunction "1_1") (pintype "passive"))
      (node (ref "R60") (pin "1") (pinfunction "1_1") (pintype "passive"))
      (node (ref "R70") (pin "1") (pinfunction "1_1") (pintype "passive"))
      (node (ref "R71") (pin "1") (pinfunction "1_1") (pintype "passive"))
      (node (ref "R73") (pin "1") (pinfunction "1_1") (pintype "passive"))
      (node (ref "R78") (pin "1") (pinfunction "1_1") (pintype "passive"))
      (node (ref "R82") (pin "1") (pinfunction "1_1") (pintype "passive"))
      (node (ref "R84") (pin "1") (pinfunction "1_1") (pintype "passive"))
      (node (ref "R86") (pin "1") (pinfunction "1_1") (pintype "passive"))
      (node (ref "R88") (pin "1") (pinfunction "1_1") (pintype "passive"))
      (node (ref "S1") (pin "1") (pinfunction "1_1") (pintype "passive"))
      (node (ref "S1") (pin "2") (pinfunction "2_2") (pintype "passive"))
      (node (ref "S1") (pin "3") (pinfunction "3_3") (pintype "passive"))
      (node (ref "S1") (pin "4") (pinfunction "4_4") (pintype "passive"))
      (node (ref "S1") (pin "5") (pinfunction "5_5") (pintype "passive"))
      (node (ref "U1") (pin "9") (pinfunction "VSS_9") (pintype "bidirectional"))
      (node (ref "U10") (pin "4") (pinfunction "V-_4") (pintype "power_in"))
      (node (ref "U11") (pin "2") (pinfunction "GND_2") (pintype "bidirectional"))
      (node (ref "U11") (pin "4") (pinfunction "IN-_4") (pintype "bidirectional"))
      (node (ref "U12") (pin "2") (pinfunction "GND_2") (pintype "bidirectional"))
      (node (ref "U13") (pin "3") (pinfunction "GND_3") (pintype "bidirectional"))
      (node (ref "U14") (pin "7") (pinfunction "GND_7") (pintype "bidirectional"))
      (node (ref "U14") (pin "PAD") (pinfunction "GND_PAD") (pintype "bidirectional"))
      (node (ref "U2") (pin "2") (pinfunction "VSS_2") (pintype "bidirectional"))
      (node (ref "U3") (pin "11") (pinfunction "S1_11") (pintype "bidirectional"))
      (node (ref "U3") (pin "12") (pinfunction "1Y0_12") (pintype "bidirectional"))
      (node (ref "U3") (pin "13") (pinfunction "1Y1_13") (pintype "bidirectional"))
      (node (ref "U3") (pin "14") (pinfunction "1Z_14") (pintype "input"))
      (node (ref "U3") (pin "6") (pinfunction "E_6") (pintype "input"))
      (node (ref "U3") (pin "7") (pinfunction "VEE_7") (pintype "power_in"))
      (node (ref "U3") (pin "8") (pinfunction "GND_8") (pintype "power_in"))
      (node (ref "U4") (pin "19") (pinfunction "GND_19") (pintype "bidirectional"))
      (node (ref "U4") (pin "29") (pinfunction "GND_29") (pintype "bidirectional"))
      (node (ref "U5") (pin "1") (pinfunction "A0_1") (pintype "input"))
      (node (ref "U5") (pin "2") (pinfunction "A1_2") (pintype "input"))
      (node (ref "U5") (pin "3") (pinfunction "A2_3") (pintype "input"))
      (node (ref "U5") (pin "4") (pinfunction "GND_4") (pintype "power_in"))
      (node (ref "U5") (pin "7") (pinfunction "WP_7") (pintype "input"))
      (node (ref "U6") (pin "19") (pinfunction "GND_19") (pintype "bidirectional"))
      (node (ref "U6") (pin "29") (pinfunction "GND_29") (pintype "bidirectional"))
      (node (ref "U7") (pin "6") (pinfunction "E_6") (pintype "input"))
      (node (ref "U7") (pin "7") (pinfunction "VEE_7") (pintype "power_in"))
      (node (ref "U7") (pin "8") (pinfunction "GND_8") (pintype "power_in"))
      (node (ref "U8") (pin "3") (pinfunction "GND_3") (pintype "power_in"))
    )
    (net (code "73") (name "Net-(D6-C)") (class "Default")
      (node (ref "D6") (pin "3") (pinfunction "C_3") (pintype "passive"))
      (node (ref "R14") (pin "1") (pinfunction "1_1") (pintype "passive"))
      (node (ref "R2") (pin "2") (pinfunction "2_2") (pintype "passive"))
      (node (ref "R9") (pin "2") (pinfunction "2_2") (pintype "passive"))
    )
    (net (code "74") (name "Net-(D7-C)") (class "Default")
      (node (ref "D7") (pin "3") (pinfunction "C_3") (pintype "passive"))
      (node (ref "R10") (pin "2") (pinfunction "2_2") (pintype "passive"))
      (node (ref "R17") (pin "2") (pinfunction "2_2") (pintype "passive"))
      (node (ref "R18") (pin "1") (pinfunction "1_1") (pintype "passive"))
    )
    (net (code "75") (name "Net-(D8-C1)") (class "Default")
      (node (ref "D8") (pin "2") (pinfunction "C1_2") (pintype "passive"))
      (node (ref "J1") (pin "6") (pinfunction "6_6") (pintype "bidirectional"))
      (node (ref "R19") (pin "1") (pinfunction "1_1") (pintype "passive"))
      (node (ref "R20") (pin "1") (pinfunction "1_1") (pintype "passive"))
    )
    (net (code "76") (name "Net-(D8-C2)") (class "Default")
      (node (ref "D8") (pin "3") (pinfunction "C2_3") (pintype "passive"))
      (node (ref "J1") (pin "8") (pinfunction "8_8") (pintype "bidirectional"))
      (node (ref "R11") (pin "1") (pinfunction "1_1") (pintype "passive"))
      (node (ref "R21") (pin "1") (pinfunction "1_1") (pintype "passive"))
    )
    (net (code "77") (name "Net-(D8-C3)") (class "Default")
      (node (ref "D8") (pin "4") (pinfunction "C3_4") (pintype "passive"))
      (node (ref "J1") (pin "4") (pinfunction "4_4") (pintype "bidirectional"))
      (node (ref "R13") (pin "1") (pinfunction "1_1") (pintype "passive"))
    )
    (net (code "78") (name "Net-(D9-C)") (class "Default")
      (node (ref "D9") (pin "3") (pinfunction "C_3") (pintype "passive"))
      (node (ref "R24") (pin "1") (pinfunction "1_1") (pintype "passive"))
      (node (ref "R33") (pin "2") (pinfunction "2_2") (pintype "passive"))
      (node (ref "R8") (pin "2") (pinfunction "2_2") (pintype "passive"))
    )
    (net (code "79") (name "Net-(D10-C)") (class "Default")
      (node (ref "D10") (pin "3") (pinfunction "C_3") (pintype "passive"))
      (node (ref "R25") (pin "2") (pinfunction "2_2") (pintype "passive"))
      (node (ref "R26") (pin "1") (pinfunction "1_1") (pintype "passive"))
      (node (ref "R3") (pin "2") (pinfunction "2_2") (pintype "passive"))
    )
    (net (code "80") (name "Net-(D11-C)") (class "Default")
      (node (ref "D11") (pin "3") (pinfunction "C_3") (pintype "passive"))
      (node (ref "R27") (pin "2") (pinfunction "2_2") (pintype "passive"))
      (node (ref "R28") (pin "1") (pinfunction "1_1") (pintype "passive"))
      (node (ref "R4") (pin "2") (pinfunction "2_2") (pintype "passive"))
    )
    (net (code "81") (name "Net-(D12-C)") (class "Default")
      (node (ref "D12") (pin "3") (pinfunction "C_3") (pintype "passive"))
      (node (ref "R29") (pin "1") (pinfunction "1_1") (pintype "passive"))
      (node (ref "R30") (pin "2") (pinfunction "2_2") (pintype "passive"))
      (node (ref "R5") (pin "2") (pinfunction "2_2") (pintype "passive"))
    )
    (net (code "82") (name "Net-(D13-C)") (class "Default")
      (node (ref "D13") (pin "3") (pinfunction "C_3") (pintype "passive"))
      (node (ref "R31") (pin "2") (pinfunction "2_2") (pintype "passive"))
      (node (ref "R32") (pin "1") (pinfunction "1_1") (pintype "passive"))
      (node (ref "R6") (pin "2") (pinfunction "2_2") (pintype "passive"))
    )
    (net (code "83") (name "Net-(D14-C)") (class "Default")
      (node (ref "D14") (pin "3") (pinfunction "C_3") (pintype "passive"))
      (node (ref "R15") (pin "2") (pinfunction "2_2") (pintype "passive"))
      (node (ref "R23") (pin "1") (pinfunction "1_1") (pintype "passive"))
      (node (ref "R7") (pin "2") (pinfunction "2_2") (pintype "passive"))
    )
    (net (code "84") (name "Net-(D16-A)") (class "Default")
      (node (ref "D16") (pin "1") (pinfunction "A_1") (pintype "passive"))
      (node (ref "K1") (pin "12") (pinfunction "-_12") (pintype "passive"))
      (node (ref "Q3") (pin "3") (pinfunction "D_3") (pintype "passive"))
    )
    (net (code "85") (name "Net-(D17-A)") (class "Default")
      (node (ref "D17") (pin "1") (pinfunction "A_1") (pintype "passive"))
      (node (ref "K2") (pin "12") (pinfunction "-_12") (pintype "passive"))
      (node (ref "Q4") (pin "3") (pinfunction "D_3") (pintype "passive"))
    )
    (net (code "86") (name "Net-(D18-C)") (class "Default")
      (node (ref "D18") (pin "3") (pinfunction "C_3") (pintype "passive"))
      (node (ref "R50") (pin "1") (pinfunction "1_1") (pintype "passive"))
      (node (ref "R55") (pin "2") (pinfunction "2_2") (pintype "passive"))
      (node (ref "R56") (pin "2") (pinfunction "2_2") (pintype "passive"))
    )
    (net (code "87") (name "Net-(D20-C)") (class "Default")
      (node (ref "D20") (pin "3") (pinfunction "C_3") (pintype "passive"))
      (node (ref "R73") (pin "2") (pinfunction "2_2") (pintype "passive"))
      (node (ref "R80") (pin "2") (pinfunction "2_2") (pintype "passive"))
      (node (ref "R95") (pin "1") (pinfunction "1_1") (pintype "passive"))
    )
    (net (code "88") (name "Net-(D21-A)") (class "Default")
      (node (ref "D21") (pin "1") (pinfunction "A_1") (pintype "passive"))
      (node (ref "Q7") (pin "1") (pinfunction "G_1") (pintype "passive"))
      (node (ref "R63") (pin "2") (pinfunction "2_2") (pintype "passive"))
    )
    (net (code "89") (name "Net-(D23-C)") (class "Default")
      (node (ref "D23") (pin "3") (pinfunction "C_3") (pintype "passive"))
      (node (ref "R70") (pin "2") (pinfunction "2_2") (pintype "passive"))
      (node (ref "R77") (pin "2") (pinfunction "2_2") (pintype "passive"))
      (node (ref "R94") (pin "1") (pinfunction "1_1") (pintype "passive"))
    )
    (net (code "90") (name "Net-(D24-C3)") (class "Default")
      (node (ref "C34") (pin "1") (pinfunction "1_1") (pintype "passive"))
      (node (ref "C38") (pin "1") (pinfunction "1_1") (pintype "passive"))
      (node (ref "D24") (pin "4") (pinfunction "C3_4") (pintype "passive"))
      (node (ref "J10") (pin "1") (pinfunction "1_1") (pintype "passive"))
      (node (ref "R48") (pin "2") (pinfunction "2_2") (pintype "passive"))
      (node (ref "R49") (pin "2") (pinfunction "2_2") (pintype "passive"))
      (node (ref "R65") (pin "2") (pinfunction "2_2") (pintype "passive"))
      (node (ref "U13") (pin "5") (pinfunction "VCC_5") (pintype "bidirectional"))
    )
    (net (code "91") (name "Net-(D25-C1)") (class "Default")
      (node (ref "D25") (pin "2") (pinfunction "C1_2") (pintype "passive"))
      (node (ref "J11") (pin "3") (pinfunction "1_3") (pintype "passive"))
      (node (ref "R85") (pin "1") (pinfunction "1_1") (pintype "passive"))
    )
    (net (code "92") (name "Net-(D25-C2)") (class "Default")
      (node (ref "D25") (pin "3") (pinfunction "C2_3") (pintype "passive"))
      (node (ref "J11") (pin "4") (pinfunction "1_4") (pintype "passive"))
      (node (ref "R91") (pin "1") (pinfunction "1_1") (pintype "passive"))
    )
    (net (code "93") (name "Net-(D28-A)") (class "Default")
      (node (ref "D28") (pin "1") (pinfunction "A_1") (pintype "passive"))
      (node (ref "Q9") (pin "1") (pinfunction "G_1") (pintype "passive"))
      (node (ref "R89") (pin "2") (pinfunction "2_2") (pintype "passive"))
    )
    (net (code "94") (name "Net-(F1-1-Pad1A)") (class "Default")
      (node (ref "F1") (pin "1A") (pinfunction "1_1A") (pintype "passive"))
      (node (ref "F1") (pin "1B") (pinfunction "1_1B") (pintype "passive"))
      (node (ref "J14") (pin "1") (pinfunction "1_1") (pintype "passive"))
    )
    (net (code "95") (name "Net-(J2B-1)") (class "Default")
      (node (ref "D5") (pin "C") (pinfunction "C_C") (pintype "passive"))
      (node (ref "J2") (pin "2") (pinfunction "1_2") (pintype "passive"))
      (node (ref "Q2") (pin "5") (pinfunction "D_5") (pintype "passive"))
      (node (ref "Q2") (pin "6") (pinfunction "D_6") (pintype "passive"))
    )
    (net (code "96") (name "Net-(J2C-1)") (class "Default")
      (node (ref "D4") (pin "C") (pinfunction "C_C") (pintype "passive"))
      (node (ref "J2") (pin "3") (pinfunction "1_3") (pintype "passive"))
      (node (ref "Q2") (pin "7") (pinfunction "D_7") (pintype "passive"))
      (node (ref "Q2") (pin "8") (pinfunction "D_8") (pintype "passive"))
    )
    (net (code "97") (name "Net-(J2D-1)") (class "Default")
      (node (ref "D3") (pin "C") (pinfunction "C_C") (pintype "passive"))
      (node (ref "J2") (pin "4") (pinfunction "1_4") (pintype "passive"))
      (node (ref "Q1") (pin "5") (pinfunction "D_5") (pintype "passive"))
      (node (ref "Q1") (pin "6") (pinfunction "D_6") (pintype "passive"))
    )
    (net (code "98") (name "Net-(J2E-1)") (class "Default")
      (node (ref "D2") (pin "C") (pinfunction "C_C") (pintype "passive"))
      (node (ref "J2") (pin "5") (pinfunction "1_5") (pintype "passive"))
      (node (ref "Q1") (pin "7") (pinfunction "D_7") (pintype "passive"))
      (node (ref "Q1") (pin "8") (pinfunction "D_8") (pintype "passive"))
    )
    (net (code "99") (name "Net-(J4B-1)") (class "Default")
      (node (ref "J4") (pin "2") (pinfunction "1_2") (pintype "passive"))
      (node (ref "R10") (pin "1") (pinfunction "1_1") (pintype "passive"))
    )
    (net (code "100") (name "Net-(J4C-1)") (class "Default")
      (node (ref "J4") (pin "3") (pinfunction "1_3") (pintype "passive"))
      (node (ref "R9") (pin "1") (pinfunction "1_1") (pintype "passive"))
    )
    (net (code "101") (name "Net-(J6B-1)") (class "Default")
      (node (ref "J6") (pin "2") (pinfunction "1_2") (pintype "passive"))
      (node (ref "K1") (pin "9") (pinfunction "P_9") (pintype "passive"))
    )
    (net (code "102") (name "Net-(J6C-1)") (class "Default")
      (node (ref "J6") (pin "3") (pinfunction "1_3") (pintype "passive"))
      (node (ref "K1") (pin "10") (pinfunction "O_10") (pintype "passive"))
    )
    (net (code "103") (name "Net-(J8B-1)") (class "Default")
      (node (ref "J8") (pin "2") (pinfunction "1_2") (pintype "passive"))
      (node (ref "K2") (pin "9") (pinfunction "P_9") (pintype "passive"))
    )
    (net (code "104") (name "Net-(J8C-1)") (class "Default")
      (node (ref "J8") (pin "3") (pinfunction "1_3") (pintype "passive"))
      (node (ref "K2") (pin "10") (pinfunction "O_10") (pintype "passive"))
    )
    (net (code "105") (name "Net-(K1B-S)") (class "Default")
      (node (ref "J6") (pin "1") (pinfunction "1_1") (pintype "passive"))
      (node (ref "K1") (pin "8") (pinfunction "S_8") (pintype "passive"))
    )
    (net (code "106") (name "Net-(K2B-S)") (class "Default")
      (node (ref "J8") (pin "1") (pinfunction "1_1") (pintype "passive"))
      (node (ref "K2") (pin "8") (pinfunction "S_8") (pintype "passive"))
    )
    (net (code "107") (name "Net-(K3B-P)") (class "Default")
      (node (ref "K3") (pin "P1") (pinfunction "P_P1") (pintype "passive"))
      (node (ref "K3") (pin "P2") (pinfunction "P_P2") (pintype "passive"))
    )
    (net (code "108") (name "Net-(LED1-AG)") (class "Default")
      (node (ref "LED1") (pin "3") (pinfunction "AG_3") (pintype "passive"))
      (node (ref "R92") (pin "1") (pinfunction "1_1") (pintype "passive"))
    )
    (net (code "109") (name "Net-(LED1-AR)") (class "Default")
      (node (ref "LED1") (pin "1") (pinfunction "AR_1") (pintype "passive"))
      (node (ref "R93") (pin "1") (pinfunction "1_1") (pintype "passive"))
    )
    (net (code "110") (name "Net-(Q1A-G)") (class "Default")
      (node (ref "Q1") (pin "4") (pinfunction "G_4") (pintype "passive"))
      (node (ref "R35") (pin "2") (pinfunction "2_2") (pintype "passive"))
    )
    (net (code "111") (name "Net-(Q1B-G)") (class "Default")
      (node (ref "Q1") (pin "2") (pinfunction "G_2") (pintype "passive"))
      (node (ref "R37") (pin "2") (pinfunction "2_2") (pintype "passive"))
    )
    (net (code "112") (name "Net-(Q2A-G)") (class "Default")
      (node (ref "Q2") (pin "4") (pinfunction "G_4") (pintype "passive"))
      (node (ref "R22") (pin "2") (pinfunction "2_2") (pintype "passive"))
    )
    (net (code "113") (name "Net-(Q2B-G)") (class "Default")
      (node (ref "Q2") (pin "2") (pinfunction "G_2") (pintype "passive"))
      (node (ref "R36") (pin "2") (pinfunction "2_2") (pintype "passive"))
    )
    (net (code "114") (name "Net-(Q3-G)") (class "Default")
      (node (ref "Q3") (pin "1") (pinfunction "G_1") (pintype "passive"))
      (node (ref "R40") (pin "2") (pinfunction "2_2") (pintype "passive"))
    )
    (net (code "115") (name "Net-(Q4-G)") (class "Default")
      (node (ref "Q4") (pin "1") (pinfunction "G_1") (pintype "passive"))
      (node (ref "R44") (pin "2") (pinfunction "2_2") (pintype "passive"))
    )
    (net (code "116") (name "Net-(Q5-D)") (class "Default")
      (node (ref "D19") (pin "C") (pinfunction "C_C") (pintype "passive"))
      (node (ref "K3") (pin "2") (pinfunction "2_2") (pintype "passive"))
      (node (ref "Q5") (pin "3") (pinfunction "D_3") (pintype "passive"))
    )
    (net (code "117") (name "Net-(Q5-G)") (class "Default")
      (node (ref "Q5") (pin "1") (pinfunction "G_1") (pintype "passive"))
      (node (ref "R54") (pin "2") (pinfunction "2_2") (pintype "passive"))
    )
    (net (code "118") (name "Net-(Q6-D)") (class "Default")
      (node (ref "Q6") (pin "3") (pinfunction "D_3") (pintype "passive"))
      (node (ref "R63") (pin "1") (pinfunction "1_1") (pintype "passive"))
      (node (ref "R66") (pin "1") (pinfunction "1_1") (pintype "passive"))
    )
    (net (code "119") (name "Net-(Q7-D)") (class "Default")
      (node (ref "Q7") (pin "3") (pinfunction "D_3") (pintype "passive"))
      (node (ref "R56") (pin "1") (pinfunction "1_1") (pintype "passive"))
    )
    (net (code "120") (name "Net-(Q8-G)") (class "Default")
      (node (ref "Q8") (pin "1") (pinfunction "G_1") (pintype "passive"))
      (node (ref "R83") (pin "2") (pinfunction "2_2") (pintype "passive"))
    )
    (net (code "121") (name "Net-(Q9-D)") (class "Default")
      (node (ref "Q9") (pin "3") (pinfunction "D_3") (pintype "passive"))
      (node (ref "R80") (pin "1") (pinfunction "1_1") (pintype "passive"))
    )
    (net (code "122") (name "Net-(Q10-D)") (class "Default")
      (node (ref "Q10") (pin "3") (pinfunction "D_3") (pintype "passive"))
      (node (ref "R89") (pin "1") (pinfunction "1_1") (pintype "passive"))
      (node (ref "R90") (pin "1") (pinfunction "1_1") (pintype "passive"))
    )
    (net (code "123") (name "Net-(Q11-D)") (class "Default")
      (node (ref "D31") (pin "C") (pinfunction "C_C") (pintype "passive"))
      (node (ref "J13") (pin "1") (pinfunction "1_1") (pintype "passive"))
      (node (ref "Q11") (pin "4") (pinfunction "D_4") (pintype "passive"))
    )
    (net (code "124") (name "Net-(Q11-G)") (class "Default")
      (node (ref "Q11") (pin "1") (pinfunction "G_1") (pintype "passive"))
      (node (ref "R87") (pin "2") (pinfunction "2_2") (pintype "passive"))
    )
    (net (code "125") (name "Net-(R51-Pad1)") (class "Default")
      (node (ref "R51") (pin "1") (pinfunction "1_1") (pintype "passive"))
      (node (ref "S1") (pin "7") (pinfunction "7_7") (pintype "passive"))
    )
    (net (code "126") (name "Net-(R58-Pad1)") (class "Default")
      (node (ref "R58") (pin "1") (pinfunction "1_1") (pintype "passive"))
      (node (ref "S1") (pin "9") (pinfunction "9_9") (pintype "passive"))
    )
    (net (code "127") (name "Net-(R62-Pad1)") (class "Default")
      (node (ref "R62") (pin "1") (pinfunction "1_1") (pintype "passive"))
      (node (ref "R64") (pin "2") (pinfunction "2_2") (pintype "passive"))
    )
    (net (code "128") (name "Net-(R64-Pad1)") (class "Default")
      (node (ref "R64") (pin "1") (pinfunction "1_1") (pintype "passive"))
      (node (ref "S1") (pin "10") (pinfunction "10_10") (pintype "passive"))
    )
    (net (code "129") (name "Net-(R68-Pad1)") (class "Default")
      (node (ref "R68") (pin "1") (pinfunction "1_1") (pintype "passive"))
      (node (ref "R69") (pin "2") (pinfunction "2_2") (pintype "passive"))
    )
    (net (code "130") (name "Net-(R69-Pad1)") (class "Default")
      (node (ref "R69") (pin "1") (pinfunction "1_1") (pintype "passive"))
      (node (ref "S1") (pin "11") (pinfunction "11_11") (pintype "passive"))
    )
    (net (code "131") (name "Net-(R74-Pad1)") (class "Default")
      (node (ref "R74") (pin "1") (pinfunction "1_1") (pintype "passive"))
      (node (ref "S1") (pin "12") (pinfunction "12_12") (pintype "passive"))
    )
    (net (code "132") (name "Net-(U1-OSC1)") (class "Default")
      (node (ref "C2") (pin "1") (pinfunction "1_1") (pintype "passive"))
      (node (ref "U1") (pin "8") (pinfunction "OSC1_8") (pintype "bidirectional"))
      (node (ref "Y1") (pin "P$1") (pinfunction "1_P$1") (pintype "passive"))
    )
    (net (code "133") (name "Net-(U1-OSC2)") (class "Default")
      (node (ref "C1") (pin "1") (pinfunction "1_1") (pintype "passive"))
      (node (ref "U1") (pin "7") (pinfunction "OSC2_7") (pintype "bidirectional"))
      (node (ref "Y1") (pin "P$2") (pinfunction "2_P$2") (pintype "passive"))
    )
    (net (code "134") (name "Net-(U1-RXCAN)") (class "Default")
      (node (ref "U1") (pin "2") (pinfunction "RXCAN_2") (pintype "bidirectional"))
      (node (ref "U2") (pin "4") (pinfunction "RXD_4") (pintype "bidirectional"))
    )
    (net (code "135") (name "Net-(U1-TXCAN)") (class "Default")
      (node (ref "U1") (pin "1") (pinfunction "TXCAN_1") (pintype "bidirectional"))
      (node (ref "U2") (pin "1") (pinfunction "TXD_1") (pintype "bidirectional"))
    )
    (net (code "136") (name "Net-(U1-~{RESET})") (class "Default")
      (node (ref "R12") (pin "1") (pinfunction "1_1") (pintype "passive"))
      (node (ref "U1") (pin "17") (pinfunction "~{RESET}_17") (pintype "bidirectional"))
    )
    (net (code "137") (name "Net-(U1-~{RX0BF})") (class "Default")
      (node (ref "U1") (pin "11") (pinfunction "~{RX0BF}_11") (pintype "bidirectional"))
      (node (ref "U2") (pin "8") (pinfunction "STBY_8") (pintype "bidirectional"))
    )
    (net (code "138") (name "Net-(U3A-2Y1)") (class "Default")
      (node (ref "U3") (pin "1") (pinfunction "2Y1_1") (pintype "bidirectional"))
      (node (ref "U7") (pin "13") (pinfunction "1Y1_13") (pintype "bidirectional"))
    )
    (net (code "139") (name "Net-(U3A-3Y1)") (class "Default")
      (node (ref "U3") (pin "3") (pinfunction "3Y1_3") (pintype "bidirectional"))
      (node (ref "U7") (pin "1") (pinfunction "2Y1_1") (pintype "bidirectional"))
    )
    (net (code "140") (name "Net-(U3A-S2)") (class "Default")
      (node (ref "R49") (pin "1") (pinfunction "1_1") (pintype "passive"))
      (node (ref "U3") (pin "10") (pinfunction "S2_10") (pintype "bidirectional"))
      (node (ref "U3") (pin "9") (pinfunction "S3_9") (pintype "bidirectional"))
    )
    (net (code "141") (name "Net-(U6-PA0{slash}XTALHF1)") (class "Default")
      (node (ref "C28") (pin "1") (pinfunction "1_1") (pintype "passive"))
      (node (ref "R46") (pin "1") (pinfunction "1_1") (pintype "passive"))
      (node (ref "U6") (pin "30") (pinfunction "PA0/XTALHF1_30") (pintype "bidirectional"))
      (node (ref "Y2") (pin "P$2") (pinfunction "2_P$2") (pintype "passive"))
    )
    (net (code "142") (name "Net-(U6-PA1{slash}XTALHF2)") (class "Default")
      (node (ref "C20") (pin "1") (pinfunction "1_1") (pintype "passive"))
      (node (ref "U6") (pin "31") (pinfunction "PA1/XTALHF2_31") (pintype "bidirectional"))
      (node (ref "Y2") (pin "P$1") (pinfunction "1_P$1") (pintype "passive"))
    )
    (net (code "143") (name "Net-(U7A-1Y0)") (class "Default")
      (node (ref "R57") (pin "2") (pinfunction "2_2") (pintype "passive"))
      (node (ref "U7") (pin "12") (pinfunction "1Y0_12") (pintype "bidirectional"))
    )
    (net (code "144") (name "Net-(U7A-1Z)") (class "Default")
      (node (ref "R75") (pin "1") (pinfunction "1_1") (pintype "passive"))
      (node (ref "U7") (pin "14") (pinfunction "1Z_14") (pintype "input"))
    )
    (net (code "145") (name "Net-(U7A-2Z)") (class "Default")
      (node (ref "R79") (pin "1") (pinfunction "1_1") (pintype "passive"))
      (node (ref "U7") (pin "15") (pinfunction "2Z_15") (pintype "input"))
    )
    (net (code "146") (name "Net-(U8A-O)") (class "Default")
      (node (ref "R54") (pin "1") (pinfunction "1_1") (pintype "passive"))
      (node (ref "R60") (pin "2") (pinfunction "2_2") (pintype "passive"))
      (node (ref "U8") (pin "4") (pinfunction "O_4") (pintype "output"))
    )
    (net (code "147") (name "Net-(U10A-+IN)") (class "Default")
      (node (ref "R96") (pin "2") (pinfunction "2_2") (pintype "passive"))
      (node (ref "U10") (pin "3") (pinfunction "+IN_3") (pintype "input"))
      (node (ref "U10") (pin "5") (pinfunction "+IN_5") (pintype "input"))
    )
    (net (code "148") (name "Net-(U10A--IN)") (class "Default")
      (node (ref "R76") (pin "1") (pinfunction "1_1") (pintype "passive"))
      (node (ref "U10") (pin "1") (pinfunction "OUT_1") (pintype "output"))
      (node (ref "U10") (pin "2") (pinfunction "-IN_2") (pintype "input"))
    )
    (net (code "149") (name "Net-(U10B--IN)") (class "Default")
      (node (ref "R97") (pin "1") (pinfunction "1_1") (pintype "passive"))
      (node (ref "U10") (pin "6") (pinfunction "-IN_6") (pintype "input"))
      (node (ref "U10") (pin "7") (pinfunction "OUT_7") (pintype "output"))
    )
    (net (code "150") (name "Net-(U11-OUT)") (class "Default")
      (node (ref "R82") (pin "2") (pinfunction "2_2") (pintype "passive"))
      (node (ref "R83") (pin "1") (pinfunction "1_1") (pintype "passive"))
      (node (ref "U11") (pin "5") (pinfunction "OUT_5") (pintype "bidirectional"))
    )
    (net (code "151") (name "Net-(U12-ILIM)") (class "Default")
      (node (ref "R71") (pin "2") (pinfunction "2_2") (pintype "passive"))
      (node (ref "U12") (pin "5") (pinfunction "ILIM_5") (pintype "bidirectional"))
    )
    (net (code "152") (name "Net-(U13-RXD)") (class "Default")
      (node (ref "R79") (pin "2") (pinfunction "2_2") (pintype "passive"))
      (node (ref "U13") (pin "7") (pinfunction "RXD_7") (pintype "bidirectional"))
    )
    (net (code "153") (name "Net-(U13-TXD)") (class "Default")
      (node (ref "R75") (pin "2") (pinfunction "2_2") (pintype "passive"))
      (node (ref "U13") (pin "6") (pinfunction "TXD_6") (pintype "bidirectional"))
    )
    (net (code "154") (name "Net-(U13-V3)") (class "Default")
      (node (ref "C37") (pin "1") (pinfunction "1_1") (pintype "passive"))
      (node (ref "U13") (pin "8") (pinfunction "V3_8") (pintype "bidirectional"))
    )
    (net (code "155") (name "Net-(U14-BST)") (class "Default")
      (node (ref "C49") (pin "1") (pinfunction "1_1") (pintype "passive"))
      (node (ref "U14") (pin "1") (pinfunction "BST_1") (pintype "bidirectional"))
    )
    (net (code "156") (name "Net-(U14-EN)") (class "Default")
      (node (ref "C47") (pin "+") (pinfunction "+_+") (pintype "passive"))
      (node (ref "C50") (pin "1") (pinfunction "1_1") (pintype "passive"))
      (node (ref "C51") (pin "1") (pinfunction "1_1") (pintype "passive"))
      (node (ref "D29") (pin "C") (pinfunction "C_C") (pintype "passive"))
      (node (ref "U14") (pin "2") (pinfunction "VIN_2") (pintype "bidirectional"))
      (node (ref "U14") (pin "3") (pinfunction "EN_3") (pintype "bidirectional"))
    )
    (net (code "157") (name "Net-(U14-FB)") (class "Default")
      (node (ref "R81") (pin "1") (pinfunction "1_1") (pintype "passive"))
      (node (ref "R84") (pin "2") (pinfunction "2_2") (pintype "passive"))
      (node (ref "U14") (pin "5") (pinfunction "FB_5") (pintype "bidirectional"))
    )
    (net (code "158") (name "Net-(U14-RT{slash}CLK)") (class "Default")
      (node (ref "R88") (pin "2") (pinfunction "2_2") (pintype "passive"))
      (node (ref "U14") (pin "4") (pinfunction "RT/CLK_4") (pintype "bidirectional"))
    )
    (net (code "159") (name "Net-(U14-SS)") (class "Default")
      (node (ref "C42") (pin "1") (pinfunction "1_1") (pintype "passive"))
      (node (ref "U14") (pin "6") (pinfunction "SS_6") (pintype "bidirectional"))
    )
    (net (code "160") (name "Net-(U14-SW)") (class "Default")
      (node (ref "C49") (pin "2") (pinfunction "2_2") (pintype "passive"))
      (node (ref "L1") (pin "1") (pinfunction "1_1") (pintype "passive"))
      (node (ref "U14") (pin "8") (pinfunction "SW_8") (pintype "bidirectional"))
    )
    (net (code "161") (name "unconnected-(D16-AC-Pad3)") (class "Default")
      (node (ref "D16") (pin "3") (pinfunction "AC_3") (pintype "passive"))
    )
    (net (code "162") (name "unconnected-(D17-AC-Pad3)") (class "Default")
      (node (ref "D17") (pin "3") (pinfunction "AC_3") (pintype "passive"))
    )
    (net (code "163") (name "unconnected-(J5-L4-Pad4L)") (class "Default")
      (node (ref "J5") (pin "4L") (pinfunction "L4_4L") (pintype "bidirectional"))
    )
    (net (code "164") (name "unconnected-(J5-L5-Pad5L)") (class "Default")
      (node (ref "J5") (pin "5L") (pinfunction "L5_5L") (pintype "bidirectional"))
    )
    (net (code "165") (name "unconnected-(J5-L8-Pad8L)") (class "Default")
      (node (ref "J5") (pin "8L") (pinfunction "L8_8L") (pintype "bidirectional"))
    )
    (net (code "166") (name "unconnected-(J5-R4-Pad4R)") (class "Default")
      (node (ref "J5") (pin "4R") (pinfunction "R4_4R") (pintype "bidirectional"))
    )
    (net (code "167") (name "unconnected-(J5-R5-Pad5R)") (class "Default")
      (node (ref "J5") (pin "5R") (pinfunction "R5_5R") (pintype "bidirectional"))
    )
    (net (code "168") (name "unconnected-(J5-R8-Pad8R)") (class "Default")
      (node (ref "J5") (pin "8R") (pinfunction "R8_8R") (pintype "bidirectional"))
    )
    (net (code "169") (name "unconnected-(K3B-O-PadO1)") (class "Default")
      (node (ref "K3") (pin "O1") (pinfunction "O_O1") (pintype "passive"))
    )
    (net (code "170") (name "unconnected-(K3C-O-PadO2)") (class "Default")
      (node (ref "K3") (pin "O2") (pinfunction "O_O2") (pintype "passive"))
    )
    (net (code "171") (name "unconnected-(U1-~{RX1BF}-Pad10)") (class "Default")
      (node (ref "U1") (pin "10") (pinfunction "~{RX1BF}_10") (pintype "bidirectional"))
    )
    (net (code "172") (name "unconnected-(U1-~{TX0RTS}-Pad4)") (class "Default")
      (node (ref "U1") (pin "4") (pinfunction "~{TX0RTS}_4") (pintype "bidirectional"))
    )
    (net (code "173") (name "unconnected-(U1-~{TX1RTS}-Pad5)") (class "Default")
      (node (ref "U1") (pin "5") (pinfunction "~{TX1RTS}_5") (pintype "bidirectional"))
    )
    (net (code "174") (name "unconnected-(U1-~{TX2RTS}-Pad6)") (class "Default")
      (node (ref "U1") (pin "6") (pinfunction "~{TX2RTS}_6") (pintype "bidirectional"))
    )
  )
)
